# smd-practice-manufactured-2016-10-13.net
KiCad netlist of a schematic drawn in EAGLE
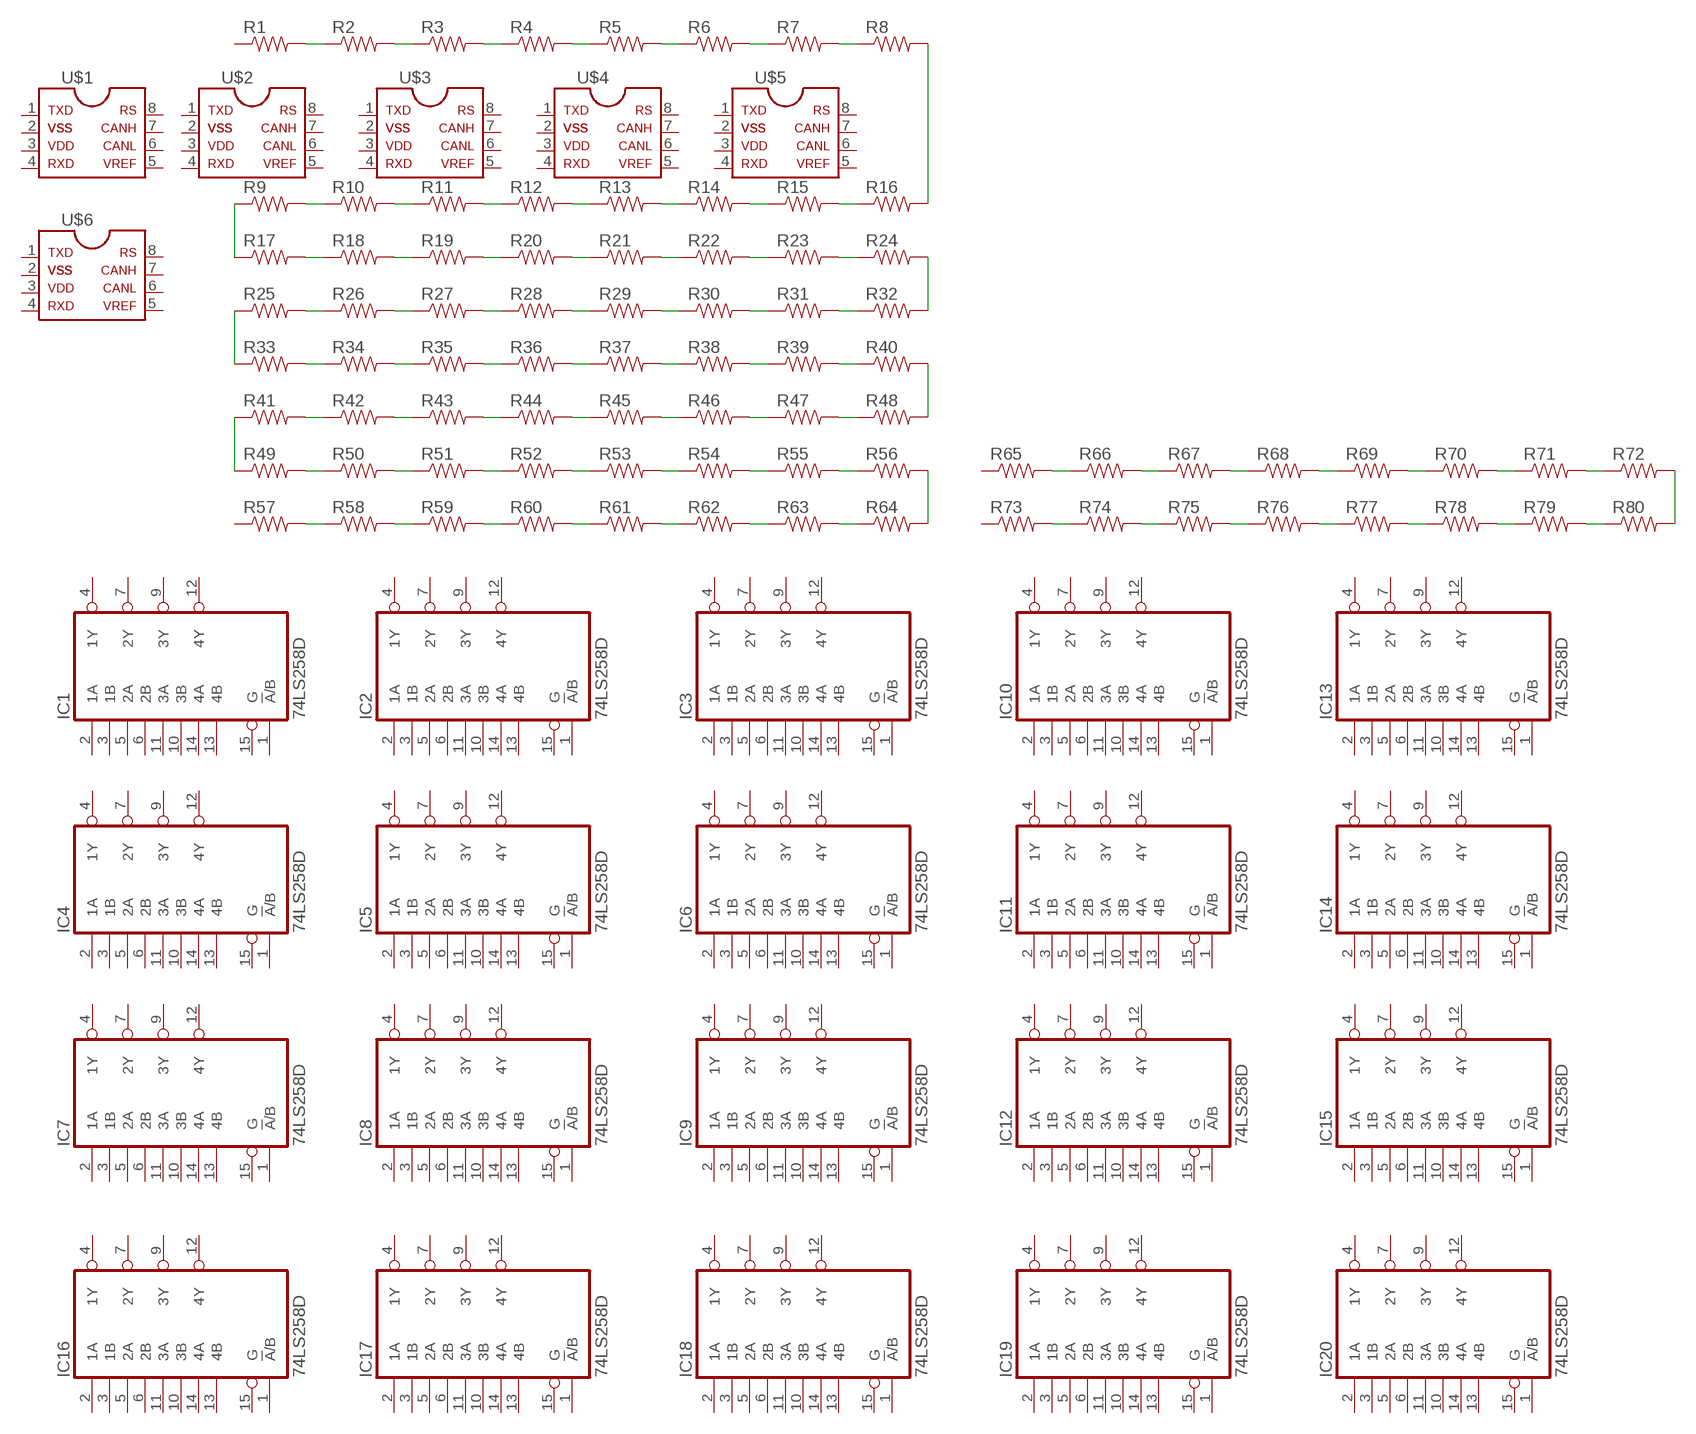
[diagram p0: schematic, sheet 1]

(export (version "E")
  (design (tool "Eeschema 10.0.6"))
  (components
    (comp (ref "IC1")
      (value "74LS258D")
      (footprint "eagle-import:SO16")
      (libsource (lib "eagle-import") (part "74258DLS"))
    )
    (comp (ref "IC2")
      (value "74LS258D")
      (footprint "eagle-import:SO16")
      (libsource (lib "eagle-import") (part "74258DLS"))
    )
    (comp (ref "IC3")
      (value "74LS258D")
      (footprint "eagle-import:SO16")
      (libsource (lib "eagle-import") (part "74258DLS"))
    )
    (comp (ref "IC4")
      (value "74LS258D")
      (footprint "eagle-import:SO16")
      (libsource (lib "eagle-import") (part "74258DLS"))
    )
    (comp (ref "IC5")
      (value "74LS258D")
      (footprint "eagle-import:SO16")
      (libsource (lib "eagle-import") (part "74258DLS"))
    )
    (comp (ref "IC6")
      (value "74LS258D")
      (footprint "eagle-import:SO16")
      (libsource (lib "eagle-import") (part "74258DLS"))
    )
    (comp (ref "IC7")
      (value "74LS258D")
      (footprint "eagle-import:SO16")
      (libsource (lib "eagle-import") (part "74258DLS"))
    )
    (comp (ref "IC8")
      (value "74LS258D")
      (footprint "eagle-import:SO16")
      (libsource (lib "eagle-import") (part "74258DLS"))
    )
    (comp (ref "IC9")
      (value "74LS258D")
      (footprint "eagle-import:SO16")
      (libsource (lib "eagle-import") (part "74258DLS"))
    )
    (comp (ref "IC10")
      (value "74LS258D")
      (footprint "eagle-import:SO16")
      (libsource (lib "eagle-import") (part "74258DLS"))
    )
    (comp (ref "IC11")
      (value "74LS258D")
      (footprint "eagle-import:SO16")
      (libsource (lib "eagle-import") (part "74258DLS"))
    )
    (comp (ref "IC12")
      (value "74LS258D")
      (footprint "eagle-import:SO16")
      (libsource (lib "eagle-import") (part "74258DLS"))
    )
    (comp (ref "IC13")
      (value "74LS258D")
      (footprint "eagle-import:SO16")
      (libsource (lib "eagle-import") (part "74258DLS"))
    )
    (comp (ref "IC14")
      (value "74LS258D")
      (footprint "eagle-import:SO16")
      (libsource (lib "eagle-import") (part "74258DLS"))
    )
    (comp (ref "IC15")
      (value "74LS258D")
      (footprint "eagle-import:SO16")
      (libsource (lib "eagle-import") (part "74258DLS"))
    )
    (comp (ref "IC16")
      (value "74LS258D")
      (footprint "eagle-import:SO16")
      (libsource (lib "eagle-import") (part "74258DLS"))
    )
    (comp (ref "IC17")
      (value "74LS258D")
      (footprint "eagle-import:SO16")
      (libsource (lib "eagle-import") (part "74258DLS"))
    )
    (comp (ref "IC18")
      (value "74LS258D")
      (footprint "eagle-import:SO16")
      (libsource (lib "eagle-import") (part "74258DLS"))
    )
    (comp (ref "IC19")
      (value "74LS258D")
      (footprint "eagle-import:SO16")
      (libsource (lib "eagle-import") (part "74258DLS"))
    )
    (comp (ref "IC20")
      (value "74LS258D")
      (footprint "eagle-import:SO16")
      (libsource (lib "eagle-import") (part "74258DLS"))
    )
    (comp (ref "R1")
      (value "RESISTOR0805-RES")
      (footprint "eagle-import:0805")
      (libsource (lib "eagle-import") (part "RESISTOR0805-RES"))
    )
    (comp (ref "R2")
      (value "RESISTOR0805-RES")
      (footprint "eagle-import:0805")
      (libsource (lib "eagle-import") (part "RESISTOR0805-RES"))
    )
    (comp (ref "R3")
      (value "RESISTOR0805-RES")
      (footprint "eagle-import:0805")
      (libsource (lib "eagle-import") (part "RESISTOR0805-RES"))
    )
    (comp (ref "R4")
      (value "RESISTOR0805-RES")
      (footprint "eagle-import:0805")
      (libsource (lib "eagle-import") (part "RESISTOR0805-RES"))
    )
    (comp (ref "R5")
      (value "RESISTOR0805-RES")
      (footprint "eagle-import:0805")
      (libsource (lib "eagle-import") (part "RESISTOR0805-RES"))
    )
    (comp (ref "R6")
      (value "RESISTOR0805-RES")
      (footprint "eagle-import:0805")
      (libsource (lib "eagle-import") (part "RESISTOR0805-RES"))
    )
    (comp (ref "R7")
      (value "RESISTOR0805-RES")
      (footprint "eagle-import:0805")
      (libsource (lib "eagle-import") (part "RESISTOR0805-RES"))
    )
    (comp (ref "R8")
      (value "RESISTOR0805-RES")
      (footprint "eagle-import:0805")
      (libsource (lib "eagle-import") (part "RESISTOR0805-RES"))
    )
    (comp (ref "R9")
      (value "RESISTOR0805-RES")
      (footprint "eagle-import:0805")
      (libsource (lib "eagle-import") (part "RESISTOR0805-RES"))
    )
    (comp (ref "R10")
      (value "RESISTOR0805-RES")
      (footprint "eagle-import:0805")
      (libsource (lib "eagle-import") (part "RESISTOR0805-RES"))
    )
    (comp (ref "R11")
      (value "RESISTOR0805-RES")
      (footprint "eagle-import:0805")
      (libsource (lib "eagle-import") (part "RESISTOR0805-RES"))
    )
    (comp (ref "R12")
      (value "RESISTOR0805-RES")
      (footprint "eagle-import:0805")
      (libsource (lib "eagle-import") (part "RESISTOR0805-RES"))
    )
    (comp (ref "R13")
      (value "RESISTOR0805-RES")
      (footprint "eagle-import:0805")
      (libsource (lib "eagle-import") (part "RESISTOR0805-RES"))
    )
    (comp (ref "R14")
      (value "RESISTOR0805-RES")
      (footprint "eagle-import:0805")
      (libsource (lib "eagle-import") (part "RESISTOR0805-RES"))
    )
    (comp (ref "R15")
      (value "RESISTOR0805-RES")
      (footprint "eagle-import:0805")
      (libsource (lib "eagle-import") (part "RESISTOR0805-RES"))
    )
    (comp (ref "R16")
      (value "RESISTOR0805-RES")
      (footprint "eagle-import:0805")
      (libsource (lib "eagle-import") (part "RESISTOR0805-RES"))
    )
    (comp (ref "R17")
      (value "RESISTOR0805-RES")
      (footprint "eagle-import:0805")
      (libsource (lib "eagle-import") (part "RESISTOR0805-RES"))
    )
    (comp (ref "R18")
      (value "RESISTOR0805-RES")
      (footprint "eagle-import:0805")
      (libsource (lib "eagle-import") (part "RESISTOR0805-RES"))
    )
    (comp (ref "R19")
      (value "RESISTOR0805-RES")
      (footprint "eagle-import:0805")
      (libsource (lib "eagle-import") (part "RESISTOR0805-RES"))
    )
    (comp (ref "R20")
      (value "RESISTOR0805-RES")
      (footprint "eagle-import:0805")
      (libsource (lib "eagle-import") (part "RESISTOR0805-RES"))
    )
    (comp (ref "R21")
      (value "RESISTOR0805-RES")
      (footprint "eagle-import:0805")
      (libsource (lib "eagle-import") (part "RESISTOR0805-RES"))
    )
    (comp (ref "R22")
      (value "RESISTOR0805-RES")
      (footprint "eagle-import:0805")
      (libsource (lib "eagle-import") (part "RESISTOR0805-RES"))
    )
    (comp (ref "R23")
      (value "RESISTOR0805-RES")
      (footprint "eagle-import:0805")
      (libsource (lib "eagle-import") (part "RESISTOR0805-RES"))
    )
    (comp (ref "R24")
      (value "RESISTOR0805-RES")
      (footprint "eagle-import:0805")
      (libsource (lib "eagle-import") (part "RESISTOR0805-RES"))
    )
    (comp (ref "R25")
      (value "RESISTOR0805-RES")
      (footprint "eagle-import:0805")
      (libsource (lib "eagle-import") (part "RESISTOR0805-RES"))
    )
    (comp (ref "R26")
      (value "RESISTOR0805-RES")
      (footprint "eagle-import:0805")
      (libsource (lib "eagle-import") (part "RESISTOR0805-RES"))
    )
    (comp (ref "R27")
      (value "RESISTOR0805-RES")
      (footprint "eagle-import:0805")
      (libsource (lib "eagle-import") (part "RESISTOR0805-RES"))
    )
    (comp (ref "R28")
      (value "RESISTOR0805-RES")
      (footprint "eagle-import:0805")
      (libsource (lib "eagle-import") (part "RESISTOR0805-RES"))
    )
    (comp (ref "R29")
      (value "RESISTOR0805-RES")
      (footprint "eagle-import:0805")
      (libsource (lib "eagle-import") (part "RESISTOR0805-RES"))
    )
    (comp (ref "R30")
      (value "RESISTOR0805-RES")
      (footprint "eagle-import:0805")
      (libsource (lib "eagle-import") (part "RESISTOR0805-RES"))
    )
    (comp (ref "R31")
      (value "RESISTOR0805-RES")
      (footprint "eagle-import:0805")
      (libsource (lib "eagle-import") (part "RESISTOR0805-RES"))
    )
    (comp (ref "R32")
      (value "RESISTOR0805-RES")
      (footprint "eagle-import:0805")
      (libsource (lib "eagle-import") (part "RESISTOR0805-RES"))
    )
    (comp (ref "R33")
      (value "RESISTOR0805-RES")
      (footprint "eagle-import:0805")
      (libsource (lib "eagle-import") (part "RESISTOR0805-RES"))
    )
    (comp (ref "R34")
      (value "RESISTOR0805-RES")
      (footprint "eagle-import:0805")
      (libsource (lib "eagle-import") (part "RESISTOR0805-RES"))
    )
    (comp (ref "R35")
      (value "RESISTOR0805-RES")
      (footprint "eagle-import:0805")
      (libsource (lib "eagle-import") (part "RESISTOR0805-RES"))
    )
    (comp (ref "R36")
      (value "RESISTOR0805-RES")
      (footprint "eagle-import:0805")
      (libsource (lib "eagle-import") (part "RESISTOR0805-RES"))
    )
    (comp (ref "R37")
      (value "RESISTOR0805-RES")
      (footprint "eagle-import:0805")
      (libsource (lib "eagle-import") (part "RESISTOR0805-RES"))
    )
    (comp (ref "R38")
      (value "RESISTOR0805-RES")
      (footprint "eagle-import:0805")
      (libsource (lib "eagle-import") (part "RESISTOR0805-RES"))
    )
    (comp (ref "R39")
      (value "RESISTOR0805-RES")
      (footprint "eagle-import:0805")
      (libsource (lib "eagle-import") (part "RESISTOR0805-RES"))
    )
    (comp (ref "R40")
      (value "RESISTOR0805-RES")
      (footprint "eagle-import:0805")
      (libsource (lib "eagle-import") (part "RESISTOR0805-RES"))
    )
    (comp (ref "R41")
      (value "RESISTOR0805-RES")
      (footprint "eagle-import:0805")
      (libsource (lib "eagle-import") (part "RESISTOR0805-RES"))
    )
    (comp (ref "R42")
      (value "RESISTOR0805-RES")
      (footprint "eagle-import:0805")
      (libsource (lib "eagle-import") (part "RESISTOR0805-RES"))
    )
    (comp (ref "R43")
      (value "RESISTOR0805-RES")
      (footprint "eagle-import:0805")
      (libsource (lib "eagle-import") (part "RESISTOR0805-RES"))
    )
    (comp (ref "R44")
      (value "RESISTOR0805-RES")
      (footprint "eagle-import:0805")
      (libsource (lib "eagle-import") (part "RESISTOR0805-RES"))
    )
    (comp (ref "R45")
      (value "RESISTOR0805-RES")
      (footprint "eagle-import:0805")
      (libsource (lib "eagle-import") (part "RESISTOR0805-RES"))
    )
    (comp (ref "R46")
      (value "RESISTOR0805-RES")
      (footprint "eagle-import:0805")
      (libsource (lib "eagle-import") (part "RESISTOR0805-RES"))
    )
    (comp (ref "R47")
      (value "RESISTOR0805-RES")
      (footprint "eagle-import:0805")
      (libsource (lib "eagle-import") (part "RESISTOR0805-RES"))
    )
    (comp (ref "R48")
      (value "RESISTOR0805-RES")
      (footprint "eagle-import:0805")
      (libsource (lib "eagle-import") (part "RESISTOR0805-RES"))
    )
    (comp (ref "R49")
      (value "RESISTOR0805-RES")
      (footprint "eagle-import:0805")
      (libsource (lib "eagle-import") (part "RESISTOR0805-RES"))
    )
    (comp (ref "R50")
      (value "RESISTOR0805-RES")
      (footprint "eagle-import:0805")
      (libsource (lib "eagle-import") (part "RESISTOR0805-RES"))
    )
    (comp (ref "R51")
      (value "RESISTOR0805-RES")
      (footprint "eagle-import:0805")
      (libsource (lib "eagle-import") (part "RESISTOR0805-RES"))
    )
    (comp (ref "R52")
      (value "RESISTOR0805-RES")
      (footprint "eagle-import:0805")
      (libsource (lib "eagle-import") (part "RESISTOR0805-RES"))
    )
    (comp (ref "R53")
      (value "RESISTOR0805-RES")
      (footprint "eagle-import:0805")
      (libsource (lib "eagle-import") (part "RESISTOR0805-RES"))
    )
    (comp (ref "R54")
      (value "RESISTOR0805-RES")
      (footprint "eagle-import:0805")
      (libsource (lib "eagle-import") (part "RESISTOR0805-RES"))
    )
    (comp (ref "R55")
      (value "RESISTOR0805-RES")
      (footprint "eagle-import:0805")
      (libsource (lib "eagle-import") (part "RESISTOR0805-RES"))
    )
    (comp (ref "R56")
      (value "RESISTOR0805-RES")
      (footprint "eagle-import:0805")
      (libsource (lib "eagle-import") (part "RESISTOR0805-RES"))
    )
    (comp (ref "R57")
      (value "RESISTOR0805-RES")
      (footprint "eagle-import:0805")
      (libsource (lib "eagle-import") (part "RESISTOR0805-RES"))
    )
    (comp (ref "R58")
      (value "RESISTOR0805-RES")
      (footprint "eagle-import:0805")
      (libsource (lib "eagle-import") (part "RESISTOR0805-RES"))
    )
    (comp (ref "R59")
      (value "RESISTOR0805-RES")
      (footprint "eagle-import:0805")
      (libsource (lib "eagle-import") (part "RESISTOR0805-RES"))
    )
    (comp (ref "R60")
      (value "RESISTOR0805-RES")
      (footprint "eagle-import:0805")
      (libsource (lib "eagle-import") (part "RESISTOR0805-RES"))
    )
    (comp (ref "R61")
      (value "RESISTOR0805-RES")
      (footprint "eagle-import:0805")
      (libsource (lib "eagle-import") (part "RESISTOR0805-RES"))
    )
    (comp (ref "R62")
      (value "RESISTOR0805-RES")
      (footprint "eagle-import:0805")
      (libsource (lib "eagle-import") (part "RESISTOR0805-RES"))
    )
    (comp (ref "R63")
      (value "RESISTOR0805-RES")
      (footprint "eagle-import:0805")
      (libsource (lib "eagle-import") (part "RESISTOR0805-RES"))
    )
    (comp (ref "R64")
      (value "RESISTOR0805-RES")
      (footprint "eagle-import:0805")
      (libsource (lib "eagle-import") (part "RESISTOR0805-RES"))
    )
    (comp (ref "R65")
      (value "RESISTOR0805-RES")
      (footprint "eagle-import:0805")
      (libsource (lib "eagle-import") (part "RESISTOR0805-RES"))
    )
    (comp (ref "R66")
      (value "RESISTOR0805-RES")
      (footprint "eagle-import:0805")
      (libsource (lib "eagle-import") (part "RESISTOR0805-RES"))
    )
    (comp (ref "R67")
      (value "RESISTOR0805-RES")
      (footprint "eagle-import:0805")
      (libsource (lib "eagle-import") (part "RESISTOR0805-RES"))
    )
    (comp (ref "R68")
      (value "RESISTOR0805-RES")
      (footprint "eagle-import:0805")
      (libsource (lib "eagle-import") (part "RESISTOR0805-RES"))
    )
    (comp (ref "R69")
      (value "RESISTOR0805-RES")
      (footprint "eagle-import:0805")
      (libsource (lib "eagle-import") (part "RESISTOR0805-RES"))
    )
    (comp (ref "R70")
      (value "RESISTOR0805-RES")
      (footprint "eagle-import:0805")
      (libsource (lib "eagle-import") (part "RESISTOR0805-RES"))
    )
    (comp (ref "R71")
      (value "RESISTOR0805-RES")
      (footprint "eagle-import:0805")
      (libsource (lib "eagle-import") (part "RESISTOR0805-RES"))
    )
    (comp (ref "R72")
      (value "RESISTOR0805-RES")
      (footprint "eagle-import:0805")
      (libsource (lib "eagle-import") (part "RESISTOR0805-RES"))
    )
    (comp (ref "R73")
      (value "RESISTOR0805-RES")
      (footprint "eagle-import:0805")
      (libsource (lib "eagle-import") (part "RESISTOR0805-RES"))
    )
    (comp (ref "R74")
      (value "RESISTOR0805-RES")
      (footprint "eagle-import:0805")
      (libsource (lib "eagle-import") (part "RESISTOR0805-RES"))
    )
    (comp (ref "R75")
      (value "RESISTOR0805-RES")
      (footprint "eagle-import:0805")
      (libsource (lib "eagle-import") (part "RESISTOR0805-RES"))
    )
    (comp (ref "R76")
      (value "RESISTOR0805-RES")
      (footprint "eagle-import:0805")
      (libsource (lib "eagle-import") (part "RESISTOR0805-RES"))
    )
    (comp (ref "R77")
      (value "RESISTOR0805-RES")
      (footprint "eagle-import:0805")
      (libsource (lib "eagle-import") (part "RESISTOR0805-RES"))
    )
    (comp (ref "R78")
      (value "RESISTOR0805-RES")
      (footprint "eagle-import:0805")
      (libsource (lib "eagle-import") (part "RESISTOR0805-RES"))
    )
    (comp (ref "R79")
      (value "RESISTOR0805-RES")
      (footprint "eagle-import:0805")
      (libsource (lib "eagle-import") (part "RESISTOR0805-RES"))
    )
    (comp (ref "R80")
      (value "RESISTOR0805-RES")
      (footprint "eagle-import:0805")
      (libsource (lib "eagle-import") (part "RESISTOR0805-RES"))
    )
    (comp (ref "U$1")
      (value "MCP2551")
      (footprint "eagle-import:SOIC-08")
      (libsource (lib "eagle-import") (part "MCP2551"))
    )
    (comp (ref "U$2")
      (value "MCP2551")
      (footprint "eagle-import:SOIC-08")
      (libsource (lib "eagle-import") (part "MCP2551"))
    )
    (comp (ref "U$3")
      (value "MCP2551")
      (footprint "eagle-import:SOIC-08")
      (libsource (lib "eagle-import") (part "MCP2551"))
    )
    (comp (ref "U$4")
      (value "MCP2551")
      (footprint "eagle-import:SOIC-08")
      (libsource (lib "eagle-import") (part "MCP2551"))
    )
    (comp (ref "U$5")
      (value "MCP2551")
      (footprint "eagle-import:SOIC-08")
      (libsource (lib "eagle-import") (part "MCP2551"))
    )
    (comp (ref "U$6")
      (value "MCP2551")
      (footprint "eagle-import:SOIC-08")
      (libsource (lib "eagle-import") (part "MCP2551"))
    )
  )
  (nets
    (net (code "1") (name "Net-(R1-Pad2)") (class "Default")
      (node (ref "R1") (pin "2") (pinfunction "2_2") (pintype "passive"))
      (node (ref "R2") (pin "1") (pinfunction "1_1") (pintype "passive"))
    )
    (net (code "2") (name "Net-(R2-Pad2)") (class "Default")
      (node (ref "R2") (pin "2") (pinfunction "2_2") (pintype "passive"))
      (node (ref "R3") (pin "1") (pinfunction "1_1") (pintype "passive"))
    )
    (net (code "3") (name "Net-(R3-Pad2)") (class "Default")
      (node (ref "R3") (pin "2") (pinfunction "2_2") (pintype "passive"))
      (node (ref "R4") (pin "1") (pinfunction "1_1") (pintype "passive"))
    )
    (net (code "4") (name "Net-(R4-Pad2)") (class "Default")
      (node (ref "R4") (pin "2") (pinfunction "2_2") (pintype "passive"))
      (node (ref "R5") (pin "1") (pinfunction "1_1") (pintype "passive"))
    )
    (net (code "5") (name "Net-(R5-Pad2)") (class "Default")
      (node (ref "R5") (pin "2") (pinfunction "2_2") (pintype "passive"))
      (node (ref "R6") (pin "1") (pinfunction "1_1") (pintype "passive"))
    )
    (net (code "6") (name "Net-(R6-Pad2)") (class "Default")
      (node (ref "R6") (pin "2") (pinfunction "2_2") (pintype "passive"))
      (node (ref "R7") (pin "1") (pinfunction "1_1") (pintype "passive"))
    )
    (net (code "7") (name "Net-(R7-Pad2)") (class "Default")
      (node (ref "R7") (pin "2") (pinfunction "2_2") (pintype "passive"))
      (node (ref "R8") (pin "1") (pinfunction "1_1") (pintype "passive"))
    )
    (net (code "8") (name "Net-(R10-Pad1)") (class "Default")
      (node (ref "R10") (pin "1") (pinfunction "1_1") (pintype "passive"))
      (node (ref "R9") (pin "2") (pinfunction "2_2") (pintype "passive"))
    )
    (net (code "9") (name "Net-(R10-Pad2)") (class "Default")
      (node (ref "R10") (pin "2") (pinfunction "2_2") (pintype "passive"))
      (node (ref "R11") (pin "1") (pinfunction "1_1") (pintype "passive"))
    )
    (net (code "10") (name "Net-(R11-Pad2)") (class "Default")
      (node (ref "R11") (pin "2") (pinfunction "2_2") (pintype "passive"))
      (node (ref "R12") (pin "1") (pinfunction "1_1") (pintype "passive"))
    )
    (net (code "11") (name "Net-(R12-Pad2)") (class "Default")
      (node (ref "R12") (pin "2") (pinfunction "2_2") (pintype "passive"))
      (node (ref "R13") (pin "1") (pinfunction "1_1") (pintype "passive"))
    )
    (net (code "12") (name "Net-(R13-Pad2)") (class "Default")
      (node (ref "R13") (pin "2") (pinfunction "2_2") (pintype "passive"))
      (node (ref "R14") (pin "1") (pinfunction "1_1") (pintype "passive"))
    )
    (net (code "13") (name "Net-(R14-Pad2)") (class "Default")
      (node (ref "R14") (pin "2") (pinfunction "2_2") (pintype "passive"))
      (node (ref "R15") (pin "1") (pinfunction "1_1") (pintype "passive"))
    )
    (net (code "14") (name "Net-(R15-Pad2)") (class "Default")
      (node (ref "R15") (pin "2") (pinfunction "2_2") (pintype "passive"))
      (node (ref "R16") (pin "1") (pinfunction "1_1") (pintype "passive"))
    )
    (net (code "15") (name "Net-(R16-Pad2)") (class "Default")
      (node (ref "R16") (pin "2") (pinfunction "2_2") (pintype "passive"))
      (node (ref "R8") (pin "2") (pinfunction "2_2") (pintype "passive"))
    )
    (net (code "16") (name "Net-(R17-Pad1)") (class "Default")
      (node (ref "R17") (pin "1") (pinfunction "1_1") (pintype "passive"))
      (node (ref "R9") (pin "1") (pinfunction "1_1") (pintype "passive"))
    )
    (net (code "17") (name "Net-(R17-Pad2)") (class "Default")
      (node (ref "R17") (pin "2") (pinfunction "2_2") (pintype "passive"))
      (node (ref "R18") (pin "1") (pinfunction "1_1") (pintype "passive"))
    )
    (net (code "18") (name "Net-(R18-Pad2)") (class "Default")
      (node (ref "R18") (pin "2") (pinfunction "2_2") (pintype "passive"))
      (node (ref "R19") (pin "1") (pinfunction "1_1") (pintype "passive"))
    )
    (net (code "19") (name "Net-(R19-Pad2)") (class "Default")
      (node (ref "R19") (pin "2") (pinfunction "2_2") (pintype "passive"))
      (node (ref "R20") (pin "1") (pinfunction "1_1") (pintype "passive"))
    )
    (net (code "20") (name "Net-(R20-Pad2)") (class "Default")
      (node (ref "R20") (pin "2") (pinfunction "2_2") (pintype "passive"))
      (node (ref "R21") (pin "1") (pinfunction "1_1") (pintype "passive"))
    )
    (net (code "21") (name "Net-(R21-Pad2)") (class "Default")
      (node (ref "R21") (pin "2") (pinfunction "2_2") (pintype "passive"))
      (node (ref "R22") (pin "1") (pinfunction "1_1") (pintype "passive"))
    )
    (net (code "22") (name "Net-(R22-Pad2)") (class "Default")
      (node (ref "R22") (pin "2") (pinfunction "2_2") (pintype "passive"))
      (node (ref "R23") (pin "1") (pinfunction "1_1") (pintype "passive"))
    )
    (net (code "23") (name "Net-(R23-Pad2)") (class "Default")
      (node (ref "R23") (pin "2") (pinfunction "2_2") (pintype "passive"))
      (node (ref "R24") (pin "1") (pinfunction "1_1") (pintype "passive"))
    )
    (net (code "24") (name "Net-(R24-Pad2)") (class "Default")
      (node (ref "R24") (pin "2") (pinfunction "2_2") (pintype "passive"))
      (node (ref "R32") (pin "2") (pinfunction "2_2") (pintype "passive"))
    )
    (net (code "25") (name "Net-(R25-Pad1)") (class "Default")
      (node (ref "R25") (pin "1") (pinfunction "1_1") (pintype "passive"))
      (node (ref "R33") (pin "1") (pinfunction "1_1") (pintype "passive"))
    )
    (net (code "26") (name "Net-(R25-Pad2)") (class "Default")
      (node (ref "R25") (pin "2") (pinfunction "2_2") (pintype "passive"))
      (node (ref "R26") (pin "1") (pinfunction "1_1") (pintype "passive"))
    )
    (net (code "27") (name "Net-(R26-Pad2)") (class "Default")
      (node (ref "R26") (pin "2") (pinfunction "2_2") (pintype "passive"))
      (node (ref "R27") (pin "1") (pinfunction "1_1") (pintype "passive"))
    )
    (net (code "28") (name "Net-(R27-Pad2)") (class "Default")
      (node (ref "R27") (pin "2") (pinfunction "2_2") (pintype "passive"))
      (node (ref "R28") (pin "1") (pinfunction "1_1") (pintype "passive"))
    )
    (net (code "29") (name "Net-(R28-Pad2)") (class "Default")
      (node (ref "R28") (pin "2") (pinfunction "2_2") (pintype "passive"))
      (node (ref "R29") (pin "1") (pinfunction "1_1") (pintype "passive"))
    )
    (net (code "30") (name "Net-(R29-Pad2)") (class "Default")
      (node (ref "R29") (pin "2") (pinfunction "2_2") (pintype "passive"))
      (node (ref "R30") (pin "1") (pinfunction "1_1") (pintype "passive"))
    )
    (net (code "31") (name "Net-(R30-Pad2)") (class "Default")
      (node (ref "R30") (pin "2") (pinfunction "2_2") (pintype "passive"))
      (node (ref "R31") (pin "1") (pinfunction "1_1") (pintype "passive"))
    )
    (net (code "32") (name "Net-(R31-Pad2)") (class "Default")
      (node (ref "R31") (pin "2") (pinfunction "2_2") (pintype "passive"))
      (node (ref "R32") (pin "1") (pinfunction "1_1") (pintype "passive"))
    )
    (net (code "33") (name "Net-(R33-Pad2)") (class "Default")
      (node (ref "R33") (pin "2") (pinfunction "2_2") (pintype "passive"))
      (node (ref "R34") (pin "1") (pinfunction "1_1") (pintype "passive"))
    )
    (net (code "34") (name "Net-(R34-Pad2)") (class "Default")
      (node (ref "R34") (pin "2") (pinfunction "2_2") (pintype "passive"))
      (node (ref "R35") (pin "1") (pinfunction "1_1") (pintype "passive"))
    )
    (net (code "35") (name "Net-(R35-Pad2)") (class "Default")
      (node (ref "R35") (pin "2") (pinfunction "2_2") (pintype "passive"))
      (node (ref "R36") (pin "1") (pinfunction "1_1") (pintype "passive"))
    )
    (net (code "36") (name "Net-(R36-Pad2)") (class "Default")
      (node (ref "R36") (pin "2") (pinfunction "2_2") (pintype "passive"))
      (node (ref "R37") (pin "1") (pinfunction "1_1") (pintype "passive"))
    )
    (net (code "37") (name "Net-(R37-Pad2)") (class "Default")
      (node (ref "R37") (pin "2") (pinfunction "2_2") (pintype "passive"))
      (node (ref "R38") (pin "1") (pinfunction "1_1") (pintype "passive"))
    )
    (net (code "38") (name "Net-(R38-Pad2)") (class "Default")
      (node (ref "R38") (pin "2") (pinfunction "2_2") (pintype "passive"))
      (node (ref "R39") (pin "1") (pinfunction "1_1") (pintype "passive"))
    )
    (net (code "39") (name "Net-(R39-Pad2)") (class "Default")
      (node (ref "R39") (pin "2") (pinfunction "2_2") (pintype "passive"))
      (node (ref "R40") (pin "1") (pinfunction "1_1") (pintype "passive"))
    )
    (net (code "40") (name "Net-(R40-Pad2)") (class "Default")
      (node (ref "R40") (pin "2") (pinfunction "2_2") (pintype "passive"))
      (node (ref "R48") (pin "2") (pinfunction "2_2") (pintype "passive"))
    )
    (net (code "41") (name "Net-(R41-Pad1)") (class "Default")
      (node (ref "R41") (pin "1") (pinfunction "1_1") (pintype "passive"))
      (node (ref "R49") (pin "1") (pinfunction "1_1") (pintype "passive"))
    )
    (net (code "42") (name "Net-(R41-Pad2)") (class "Default")
      (node (ref "R41") (pin "2") (pinfunction "2_2") (pintype "passive"))
      (node (ref "R42") (pin "1") (pinfunction "1_1") (pintype "passive"))
    )
    (net (code "43") (name "Net-(R42-Pad2)") (class "Default")
      (node (ref "R42") (pin "2") (pinfunction "2_2") (pintype "passive"))
      (node (ref "R43") (pin "1") (pinfunction "1_1") (pintype "passive"))
    )
    (net (code "44") (name "Net-(R43-Pad2)") (class "Default")
      (node (ref "R43") (pin "2") (pinfunction "2_2") (pintype "passive"))
      (node (ref "R44") (pin "1") (pinfunction "1_1") (pintype "passive"))
    )
    (net (code "45") (name "Net-(R44-Pad2)") (class "Default")
      (node (ref "R44") (pin "2") (pinfunction "2_2") (pintype "passive"))
      (node (ref "R45") (pin "1") (pinfunction "1_1") (pintype "passive"))
    )
    (net (code "46") (name "Net-(R45-Pad2)") (class "Default")
      (node (ref "R45") (pin "2") (pinfunction "2_2") (pintype "passive"))
      (node (ref "R46") (pin "1") (pinfunction "1_1") (pintype "passive"))
    )
    (net (code "47") (name "Net-(R46-Pad2)") (class "Default")
      (node (ref "R46") (pin "2") (pinfunction "2_2") (pintype "passive"))
      (node (ref "R47") (pin "1") (pinfunction "1_1") (pintype "passive"))
    )
    (net (code "48") (name "Net-(R47-Pad2)") (class "Default")
      (node (ref "R47") (pin "2") (pinfunction "2_2") (pintype "passive"))
      (node (ref "R48") (pin "1") (pinfunction "1_1") (pintype "passive"))
    )
    (net (code "49") (name "Net-(R49-Pad2)") (class "Default")
      (node (ref "R49") (pin "2") (pinfunction "2_2") (pintype "passive"))
      (node (ref "R50") (pin "1") (pinfunction "1_1") (pintype "passive"))
    )
    (net (code "50") (name "Net-(R50-Pad2)") (class "Default")
      (node (ref "R50") (pin "2") (pinfunction "2_2") (pintype "passive"))
      (node (ref "R51") (pin "1") (pinfunction "1_1") (pintype "passive"))
    )
    (net (code "51") (name "Net-(R51-Pad2)") (class "Default")
      (node (ref "R51") (pin "2") (pinfunction "2_2") (pintype "passive"))
      (node (ref "R52") (pin "1") (pinfunction "1_1") (pintype "passive"))
    )
    (net (code "52") (name "Net-(R52-Pad2)") (class "Default")
      (node (ref "R52") (pin "2") (pinfunction "2_2") (pintype "passive"))
      (node (ref "R53") (pin "1") (pinfunction "1_1") (pintype "passive"))
    )
    (net (code "53") (name "Net-(R53-Pad2)") (class "Default")
      (node (ref "R53") (pin "2") (pinfunction "2_2") (pintype "passive"))
      (node (ref "R54") (pin "1") (pinfunction "1_1") (pintype "passive"))
    )
    (net (code "54") (name "Net-(R54-Pad2)") (class "Default")
      (node (ref "R54") (pin "2") (pinfunction "2_2") (pintype "passive"))
      (node (ref "R55") (pin "1") (pinfunction "1_1") (pintype "passive"))
    )
    (net (code "55") (name "Net-(R55-Pad2)") (class "Default")
      (node (ref "R55") (pin "2") (pinfunction "2_2") (pintype "passive"))
      (node (ref "R56") (pin "1") (pinfunction "1_1") (pintype "passive"))
    )
    (net (code "56") (name "Net-(R56-Pad2)") (class "Default")
      (node (ref "R56") (pin "2") (pinfunction "2_2") (pintype "passive"))
      (node (ref "R64") (pin "2") (pinfunction "2_2") (pintype "passive"))
    )
    (net (code "57") (name "Net-(R57-Pad2)") (class "Default")
      (node (ref "R57") (pin "2") (pinfunction "2_2") (pintype "passive"))
      (node (ref "R58") (pin "1") (pinfunction "1_1") (pintype "passive"))
    )
    (net (code "58") (name "Net-(R58-Pad2)") (class "Default")
      (node (ref "R58") (pin "2") (pinfunction "2_2") (pintype "passive"))
      (node (ref "R59") (pin "1") (pinfunction "1_1") (pintype "passive"))
    )
    (net (code "59") (name "Net-(R59-Pad2)") (class "Default")
      (node (ref "R59") (pin "2") (pinfunction "2_2") (pintype "passive"))
      (node (ref "R60") (pin "1") (pinfunction "1_1") (pintype "passive"))
    )
    (net (code "60") (name "Net-(R60-Pad2)") (class "Default")
      (node (ref "R60") (pin "2") (pinfunction "2_2") (pintype "passive"))
      (node (ref "R61") (pin "1") (pinfunction "1_1") (pintype "passive"))
    )
    (net (code "61") (name "Net-(R61-Pad2)") (class "Default")
      (node (ref "R61") (pin "2") (pinfunction "2_2") (pintype "passive"))
      (node (ref "R62") (pin "1") (pinfunction "1_1") (pintype "passive"))
    )
    (net (code "62") (name "Net-(R62-Pad2)") (class "Default")
      (node (ref "R62") (pin "2") (pinfunction "2_2") (pintype "passive"))
      (node (ref "R63") (pin "1") (pinfunction "1_1") (pintype "passive"))
    )
    (net (code "63") (name "Net-(R63-Pad2)") (class "Default")
      (node (ref "R63") (pin "2") (pinfunction "2_2") (pintype "passive"))
      (node (ref "R64") (pin "1") (pinfunction "1_1") (pintype "passive"))
    )
    (net (code "64") (name "Net-(R65-Pad2)") (class "Default")
      (node (ref "R65") (pin "2") (pinfunction "2_2") (pintype "passive"))
      (node (ref "R66") (pin "1") (pinfunction "1_1") (pintype "passive"))
    )
    (net (code "65") (name "Net-(R66-Pad2)") (class "Default")
      (node (ref "R66") (pin "2") (pinfunction "2_2") (pintype "passive"))
      (node (ref "R67") (pin "1") (pinfunction "1_1") (pintype "passive"))
    )
    (net (code "66") (name "Net-(R67-Pad2)") (class "Default")
      (node (ref "R67") (pin "2") (pinfunction "2_2") (pintype "passive"))
      (node (ref "R68") (pin "1") (pinfunction "1_1") (pintype "passive"))
    )
    (net (code "67") (name "Net-(R68-Pad2)") (class "Default")
      (node (ref "R68") (pin "2") (pinfunction "2_2") (pintype "passive"))
      (node (ref "R69") (pin "1") (pinfunction "1_1") (pintype "passive"))
    )
    (net (code "68") (name "Net-(R69-Pad2)") (class "Default")
      (node (ref "R69") (pin "2") (pinfunction "2_2") (pintype "passive"))
      (node (ref "R70") (pin "1") (pinfunction "1_1") (pintype "passive"))
    )
    (net (code "69") (name "Net-(R70-Pad2)") (class "Default")
      (node (ref "R70") (pin "2") (pinfunction "2_2") (pintype "passive"))
      (node (ref "R71") (pin "1") (pinfunction "1_1") (pintype "passive"))
    )
    (net (code "70") (name "Net-(R71-Pad2)") (class "Default")
      (node (ref "R71") (pin "2") (pinfunction "2_2") (pintype "passive"))
      (node (ref "R72") (pin "1") (pinfunction "1_1") (pintype "passive"))
    )
    (net (code "71") (name "Net-(R72-Pad2)") (class "Default")
      (node (ref "R72") (pin "2") (pinfunction "2_2") (pintype "passive"))
      (node (ref "R80") (pin "2") (pinfunction "2_2") (pintype "passive"))
    )
    (net (code "72") (name "Net-(R73-Pad2)") (class "Default")
      (node (ref "R73") (pin "2") (pinfunction "2_2") (pintype "passive"))
      (node (ref "R74") (pin "1") (pinfunction "1_1") (pintype "passive"))
    )
    (net (code "73") (name "Net-(R74-Pad2)") (class "Default")
      (node (ref "R74") (pin "2") (pinfunction "2_2") (pintype "passive"))
      (node (ref "R75") (pin "1") (pinfunction "1_1") (pintype "passive"))
    )
    (net (code "74") (name "Net-(R75-Pad2)") (class "Default")
      (node (ref "R75") (pin "2") (pinfunction "2_2") (pintype "passive"))
      (node (ref "R76") (pin "1") (pinfunction "1_1") (pintype "passive"))
    )
    (net (code "75") (name "Net-(R76-Pad2)") (class "Default")
      (node (ref "R76") (pin "2") (pinfunction "2_2") (pintype "passive"))
      (node (ref "R77") (pin "1") (pinfunction "1_1") (pintype "passive"))
    )
    (net (code "76") (name "Net-(R77-Pad2)") (class "Default")
      (node (ref "R77") (pin "2") (pinfunction "2_2") (pintype "passive"))
      (node (ref "R78") (pin "1") (pinfunction "1_1") (pintype "passive"))
    )
    (net (code "77") (name "Net-(R78-Pad2)") (class "Default")
      (node (ref "R78") (pin "2") (pinfunction "2_2") (pintype "passive"))
      (node (ref "R79") (pin "1") (pinfunction "1_1") (pintype "passive"))
    )
    (net (code "78") (name "Net-(R79-Pad2)") (class "Default")
      (node (ref "R79") (pin "2") (pinfunction "2_2") (pintype "passive"))
      (node (ref "R80") (pin "1") (pinfunction "1_1") (pintype "passive"))
    )
    (net (code "79") (name "unconnected-(IC1A-1A-Pad2)") (class "Default")
      (node (ref "IC1") (pin "2") (pinfunction "1A_2") (pintype "input"))
    )
    (net (code "80") (name "unconnected-(IC1A-1B-Pad3)") (class "Default")
      (node (ref "IC1") (pin "3") (pinfunction "1B_3") (pintype "input"))
    )
    (net (code "81") (name "unconnected-(IC1A-1Y-Pad4)") (class "Default")
      (node (ref "IC1") (pin "4") (pinfunction "1Y_4") (pintype "tri_state"))
    )
    (net (code "82") (name "unconnected-(IC1A-2A-Pad5)") (class "Default")
      (node (ref "IC1") (pin "5") (pinfunction "2A_5") (pintype "input"))
    )
    (net (code "83") (name "unconnected-(IC1A-2B-Pad6)") (class "Default")
      (node (ref "IC1") (pin "6") (pinfunction "2B_6") (pintype "input"))
    )
    (net (code "84") (name "unconnected-(IC1A-2Y-Pad7)") (class "Default")
      (node (ref "IC1") (pin "7") (pinfunction "2Y_7") (pintype "tri_state"))
    )
    (net (code "85") (name "unconnected-(IC1A-3A-Pad11)") (class "Default")
      (node (ref "IC1") (pin "11") (pinfunction "3A_11") (pintype "input"))
    )
    (net (code "86") (name "unconnected-(IC1A-3B-Pad10)") (class "Default")
      (node (ref "IC1") (pin "10") (pinfunction "3B_10") (pintype "input"))
    )
    (net (code "87") (name "unconnected-(IC1A-3Y-Pad9)") (class "Default")
      (node (ref "IC1") (pin "9") (pinfunction "3Y_9") (pintype "tri_state"))
    )
    (net (code "88") (name "unconnected-(IC1A-4A-Pad14)") (class "Default")
      (node (ref "IC1") (pin "14") (pinfunction "4A_14") (pintype "input"))
    )
    (net (code "89") (name "unconnected-(IC1A-4B-Pad13)") (class "Default")
      (node (ref "IC1") (pin "13") (pinfunction "4B_13") (pintype "input"))
    )
    (net (code "90") (name "unconnected-(IC1A-4Y-Pad12)") (class "Default")
      (node (ref "IC1") (pin "12") (pinfunction "4Y_12") (pintype "tri_state"))
    )
    (net (code "91") (name "unconnected-(IC1A-G-Pad15)") (class "Default")
      (node (ref "IC1") (pin "15") (pinfunction "G_15") (pintype "input"))
    )
    (net (code "92") (name "unconnected-(IC1A-~{A}{slash}B-Pad1)") (class "Default")
      (node (ref "IC1") (pin "1") (pinfunction "~{A}/B_1") (pintype "input"))
    )
    (net (code "93") (name "unconnected-(IC2A-1A-Pad2)") (class "Default")
      (node (ref "IC2") (pin "2") (pinfunction "1A_2") (pintype "input"))
    )
    (net (code "94") (name "unconnected-(IC2A-1B-Pad3)") (class "Default")
      (node (ref "IC2") (pin "3") (pinfunction "1B_3") (pintype "input"))
    )
    (net (code "95") (name "unconnected-(IC2A-1Y-Pad4)") (class "Default")
      (node (ref "IC2") (pin "4") (pinfunction "1Y_4") (pintype "tri_state"))
    )
    (net (code "96") (name "unconnected-(IC2A-2A-Pad5)") (class "Default")
      (node (ref "IC2") (pin "5") (pinfunction "2A_5") (pintype "input"))
    )
    (net (code "97") (name "unconnected-(IC2A-2B-Pad6)") (class "Default")
      (node (ref "IC2") (pin "6") (pinfunction "2B_6") (pintype "input"))
    )
    (net (code "98") (name "unconnected-(IC2A-2Y-Pad7)") (class "Default")
      (node (ref "IC2") (pin "7") (pinfunction "2Y_7") (pintype "tri_state"))
    )
    (net (code "99") (name "unconnected-(IC2A-3A-Pad11)") (class "Default")
      (node (ref "IC2") (pin "11") (pinfunction "3A_11") (pintype "input"))
    )
    (net (code "100") (name "unconnected-(IC2A-3B-Pad10)") (class "Default")
      (node (ref "IC2") (pin "10") (pinfunction "3B_10") (pintype "input"))
    )
    (net (code "101") (name "unconnected-(IC2A-3Y-Pad9)") (class "Default")
      (node (ref "IC2") (pin "9") (pinfunction "3Y_9") (pintype "tri_state"))
    )
    (net (code "102") (name "unconnected-(IC2A-4A-Pad14)") (class "Default")
      (node (ref "IC2") (pin "14") (pinfunction "4A_14") (pintype "input"))
    )
    (net (code "103") (name "unconnected-(IC2A-4B-Pad13)") (class "Default")
      (node (ref "IC2") (pin "13") (pinfunction "4B_13") (pintype "input"))
    )
    (net (code "104") (name "unconnected-(IC2A-4Y-Pad12)") (class "Default")
      (node (ref "IC2") (pin "12") (pinfunction "4Y_12") (pintype "tri_state"))
    )
    (net (code "105") (name "unconnected-(IC2A-G-Pad15)") (class "Default")
      (node (ref "IC2") (pin "15") (pinfunction "G_15") (pintype "input"))
    )
    (net (code "106") (name "unconnected-(IC2A-~{A}{slash}B-Pad1)") (class "Default")
      (node (ref "IC2") (pin "1") (pinfunction "~{A}/B_1") (pintype "input"))
    )
    (net (code "107") (name "unconnected-(IC3A-1A-Pad2)") (class "Default")
      (node (ref "IC3") (pin "2") (pinfunction "1A_2") (pintype "input"))
    )
    (net (code "108") (name "unconnected-(IC3A-1B-Pad3)") (class "Default")
      (node (ref "IC3") (pin "3") (pinfunction "1B_3") (pintype "input"))
    )
    (net (code "109") (name "unconnected-(IC3A-1Y-Pad4)") (class "Default")
      (node (ref "IC3") (pin "4") (pinfunction "1Y_4") (pintype "tri_state"))
    )
    (net (code "110") (name "unconnected-(IC3A-2A-Pad5)") (class "Default")
      (node (ref "IC3") (pin "5") (pinfunction "2A_5") (pintype "input"))
    )
    (net (code "111") (name "unconnected-(IC3A-2B-Pad6)") (class "Default")
      (node (ref "IC3") (pin "6") (pinfunction "2B_6") (pintype "input"))
    )
    (net (code "112") (name "unconnected-(IC3A-2Y-Pad7)") (class "Default")
      (node (ref "IC3") (pin "7") (pinfunction "2Y_7") (pintype "tri_state"))
    )
    (net (code "113") (name "unconnected-(IC3A-3A-Pad11)") (class "Default")
      (node (ref "IC3") (pin "11") (pinfunction "3A_11") (pintype "input"))
    )
    (net (code "114") (name "unconnected-(IC3A-3B-Pad10)") (class "Default")
      (node (ref "IC3") (pin "10") (pinfunction "3B_10") (pintype "input"))
    )
    (net (code "115") (name "unconnected-(IC3A-3Y-Pad9)") (class "Default")
      (node (ref "IC3") (pin "9") (pinfunction "3Y_9") (pintype "tri_state"))
    )
    (net (code "116") (name "unconnected-(IC3A-4A-Pad14)") (class "Default")
      (node (ref "IC3") (pin "14") (pinfunction "4A_14") (pintype "input"))
    )
    (net (code "117") (name "unconnected-(IC3A-4B-Pad13)") (class "Default")
      (node (ref "IC3") (pin "13") (pinfunction "4B_13") (pintype "input"))
    )
    (net (code "118") (name "unconnected-(IC3A-4Y-Pad12)") (class "Default")
      (node (ref "IC3") (pin "12") (pinfunction "4Y_12") (pintype "tri_state"))
    )
    (net (code "119") (name "unconnected-(IC3A-G-Pad15)") (class "Default")
      (node (ref "IC3") (pin "15") (pinfunction "G_15") (pintype "input"))
    )
    (net (code "120") (name "unconnected-(IC3A-~{A}{slash}B-Pad1)") (class "Default")
      (node (ref "IC3") (pin "1") (pinfunction "~{A}/B_1") (pintype "input"))
    )
    (net (code "121") (name "unconnected-(IC4A-1A-Pad2)") (class "Default")
      (node (ref "IC4") (pin "2") (pinfunction "1A_2") (pintype "input"))
    )
    (net (code "122") (name "unconnected-(IC4A-1B-Pad3)") (class "Default")
      (node (ref "IC4") (pin "3") (pinfunction "1B_3") (pintype "input"))
    )
    (net (code "123") (name "unconnected-(IC4A-1Y-Pad4)") (class "Default")
      (node (ref "IC4") (pin "4") (pinfunction "1Y_4") (pintype "tri_state"))
    )
    (net (code "124") (name "unconnected-(IC4A-2A-Pad5)") (class "Default")
      (node (ref "IC4") (pin "5") (pinfunction "2A_5") (pintype "input"))
    )
    (net (code "125") (name "unconnected-(IC4A-2B-Pad6)") (class "Default")
      (node (ref "IC4") (pin "6") (pinfunction "2B_6") (pintype "input"))
    )
    (net (code "126") (name "unconnected-(IC4A-2Y-Pad7)") (class "Default")
      (node (ref "IC4") (pin "7") (pinfunction "2Y_7") (pintype "tri_state"))
    )
    (net (code "127") (name "unconnected-(IC4A-3A-Pad11)") (class "Default")
      (node (ref "IC4") (pin "11") (pinfunction "3A_11") (pintype "input"))
    )
    (net (code "128") (name "unconnected-(IC4A-3B-Pad10)") (class "Default")
      (node (ref "IC4") (pin "10") (pinfunction "3B_10") (pintype "input"))
    )
    (net (code "129") (name "unconnected-(IC4A-3Y-Pad9)") (class "Default")
      (node (ref "IC4") (pin "9") (pinfunction "3Y_9") (pintype "tri_state"))
    )
    (net (code "130") (name "unconnected-(IC4A-4A-Pad14)") (class "Default")
      (node (ref "IC4") (pin "14") (pinfunction "4A_14") (pintype "input"))
    )
    (net (code "131") (name "unconnected-(IC4A-4B-Pad13)") (class "Default")
      (node (ref "IC4") (pin "13") (pinfunction "4B_13") (pintype "input"))
    )
    (net (code "132") (name "unconnected-(IC4A-4Y-Pad12)") (class "Default")
      (node (ref "IC4") (pin "12") (pinfunction "4Y_12") (pintype "tri_state"))
    )
    (net (code "133") (name "unconnected-(IC4A-G-Pad15)") (class "Default")
      (node (ref "IC4") (pin "15") (pinfunction "G_15") (pintype "input"))
    )
    (net (code "134") (name "unconnected-(IC4A-~{A}{slash}B-Pad1)") (class "Default")
      (node (ref "IC4") (pin "1") (pinfunction "~{A}/B_1") (pintype "input"))
    )
    (net (code "135") (name "unconnected-(IC5A-1A-Pad2)") (class "Default")
      (node (ref "IC5") (pin "2") (pinfunction "1A_2") (pintype "input"))
    )
    (net (code "136") (name "unconnected-(IC5A-1B-Pad3)") (class "Default")
      (node (ref "IC5") (pin "3") (pinfunction "1B_3") (pintype "input"))
    )
    (net (code "137") (name "unconnected-(IC5A-1Y-Pad4)") (class "Default")
      (node (ref "IC5") (pin "4") (pinfunction "1Y_4") (pintype "tri_state"))
    )
    (net (code "138") (name "unconnected-(IC5A-2A-Pad5)") (class "Default")
      (node (ref "IC5") (pin "5") (pinfunction "2A_5") (pintype "input"))
    )
    (net (code "139") (name "unconnected-(IC5A-2B-Pad6)") (class "Default")
      (node (ref "IC5") (pin "6") (pinfunction "2B_6") (pintype "input"))
    )
    (net (code "140") (name "unconnected-(IC5A-2Y-Pad7)") (class "Default")
      (node (ref "IC5") (pin "7") (pinfunction "2Y_7") (pintype "tri_state"))
    )
    (net (code "141") (name "unconnected-(IC5A-3A-Pad11)") (class "Default")
      (node (ref "IC5") (pin "11") (pinfunction "3A_11") (pintype "input"))
    )
    (net (code "142") (name "unconnected-(IC5A-3B-Pad10)") (class "Default")
      (node (ref "IC5") (pin "10") (pinfunction "3B_10") (pintype "input"))
    )
    (net (code "143") (name "unconnected-(IC5A-3Y-Pad9)") (class "Default")
      (node (ref "IC5") (pin "9") (pinfunction "3Y_9") (pintype "tri_state"))
    )
    (net (code "144") (name "unconnected-(IC5A-4A-Pad14)") (class "Default")
      (node (ref "IC5") (pin "14") (pinfunction "4A_14") (pintype "input"))
    )
    (net (code "145") (name "unconnected-(IC5A-4B-Pad13)") (class "Default")
      (node (ref "IC5") (pin "13") (pinfunction "4B_13") (pintype "input"))
    )
    (net (code "146") (name "unconnected-(IC5A-4Y-Pad12)") (class "Default")
      (node (ref "IC5") (pin "12") (pinfunction "4Y_12") (pintype "tri_state"))
    )
    (net (code "147") (name "unconnected-(IC5A-G-Pad15)") (class "Default")
      (node (ref "IC5") (pin "15") (pinfunction "G_15") (pintype "input"))
    )
    (net (code "148") (name "unconnected-(IC5A-~{A}{slash}B-Pad1)") (class "Default")
      (node (ref "IC5") (pin "1") (pinfunction "~{A}/B_1") (pintype "input"))
    )
    (net (code "149") (name "unconnected-(IC6A-1A-Pad2)") (class "Default")
      (node (ref "IC6") (pin "2") (pinfunction "1A_2") (pintype "input"))
    )
    (net (code "150") (name "unconnected-(IC6A-1B-Pad3)") (class "Default")
      (node (ref "IC6") (pin "3") (pinfunction "1B_3") (pintype "input"))
    )
    (net (code "151") (name "unconnected-(IC6A-1Y-Pad4)") (class "Default")
      (node (ref "IC6") (pin "4") (pinfunction "1Y_4") (pintype "tri_state"))
    )
    (net (code "152") (name "unconnected-(IC6A-2A-Pad5)") (class "Default")
      (node (ref "IC6") (pin "5") (pinfunction "2A_5") (pintype "input"))
    )
    (net (code "153") (name "unconnected-(IC6A-2B-Pad6)") (class "Default")
      (node (ref "IC6") (pin "6") (pinfunction "2B_6") (pintype "input"))
    )
    (net (code "154") (name "unconnected-(IC6A-2Y-Pad7)") (class "Default")
      (node (ref "IC6") (pin "7") (pinfunction "2Y_7") (pintype "tri_state"))
    )
    (net (code "155") (name "unconnected-(IC6A-3A-Pad11)") (class "Default")
      (node (ref "IC6") (pin "11") (pinfunction "3A_11") (pintype "input"))
    )
    (net (code "156") (name "unconnected-(IC6A-3B-Pad10)") (class "Default")
      (node (ref "IC6") (pin "10") (pinfunction "3B_10") (pintype "input"))
    )
    (net (code "157") (name "unconnected-(IC6A-3Y-Pad9)") (class "Default")
      (node (ref "IC6") (pin "9") (pinfunction "3Y_9") (pintype "tri_state"))
    )
    (net (code "158") (name "unconnected-(IC6A-4A-Pad14)") (class "Default")
      (node (ref "IC6") (pin "14") (pinfunction "4A_14") (pintype "input"))
    )
    (net (code "159") (name "unconnected-(IC6A-4B-Pad13)") (class "Default")
      (node (ref "IC6") (pin "13") (pinfunction "4B_13") (pintype "input"))
    )
    (net (code "160") (name "unconnected-(IC6A-4Y-Pad12)") (class "Default")
      (node (ref "IC6") (pin "12") (pinfunction "4Y_12") (pintype "tri_state"))
    )
    (net (code "161") (name "unconnected-(IC6A-G-Pad15)") (class "Default")
      (node (ref "IC6") (pin "15") (pinfunction "G_15") (pintype "input"))
    )
    (net (code "162") (name "unconnected-(IC6A-~{A}{slash}B-Pad1)") (class "Default")
      (node (ref "IC6") (pin "1") (pinfunction "~{A}/B_1") (pintype "input"))
    )
    (net (code "163") (name "unconnected-(IC7A-1A-Pad2)") (class "Default")
      (node (ref "IC7") (pin "2") (pinfunction "1A_2") (pintype "input"))
    )
    (net (code "164") (name "unconnected-(IC7A-1B-Pad3)") (class "Default")
      (node (ref "IC7") (pin "3") (pinfunction "1B_3") (pintype "input"))
    )
    (net (code "165") (name "unconnected-(IC7A-1Y-Pad4)") (class "Default")
      (node (ref "IC7") (pin "4") (pinfunction "1Y_4") (pintype "tri_state"))
    )
    (net (code "166") (name "unconnected-(IC7A-2A-Pad5)") (class "Default")
      (node (ref "IC7") (pin "5") (pinfunction "2A_5") (pintype "input"))
    )
    (net (code "167") (name "unconnected-(IC7A-2B-Pad6)") (class "Default")
      (node (ref "IC7") (pin "6") (pinfunction "2B_6") (pintype "input"))
    )
    (net (code "168") (name "unconnected-(IC7A-2Y-Pad7)") (class "Default")
      (node (ref "IC7") (pin "7") (pinfunction "2Y_7") (pintype "tri_state"))
    )
    (net (code "169") (name "unconnected-(IC7A-3A-Pad11)") (class "Default")
      (node (ref "IC7") (pin "11") (pinfunction "3A_11") (pintype "input"))
    )
    (net (code "170") (name "unconnected-(IC7A-3B-Pad10)") (class "Default")
      (node (ref "IC7") (pin "10") (pinfunction "3B_10") (pintype "input"))
    )
    (net (code "171") (name "unconnected-(IC7A-3Y-Pad9)") (class "Default")
      (node (ref "IC7") (pin "9") (pinfunction "3Y_9") (pintype "tri_state"))
    )
    (net (code "172") (name "unconnected-(IC7A-4A-Pad14)") (class "Default")
      (node (ref "IC7") (pin "14") (pinfunction "4A_14") (pintype "input"))
    )
    (net (code "173") (name "unconnected-(IC7A-4B-Pad13)") (class "Default")
      (node (ref "IC7") (pin "13") (pinfunction "4B_13") (pintype "input"))
    )
    (net (code "174") (name "unconnected-(IC7A-4Y-Pad12)") (class "Default")
      (node (ref "IC7") (pin "12") (pinfunction "4Y_12") (pintype "tri_state"))
    )
    (net (code "175") (name "unconnected-(IC7A-G-Pad15)") (class "Default")
      (node (ref "IC7") (pin "15") (pinfunction "G_15") (pintype "input"))
    )
    (net (code "176") (name "unconnected-(IC7A-~{A}{slash}B-Pad1)") (class "Default")
      (node (ref "IC7") (pin "1") (pinfunction "~{A}/B_1") (pintype "input"))
    )
    (net (code "177") (name "unconnected-(IC8A-1A-Pad2)") (class "Default")
      (node (ref "IC8") (pin "2") (pinfunction "1A_2") (pintype "input"))
    )
    (net (code "178") (name "unconnected-(IC8A-1B-Pad3)") (class "Default")
      (node (ref "IC8") (pin "3") (pinfunction "1B_3") (pintype "input"))
    )
    (net (code "179") (name "unconnected-(IC8A-1Y-Pad4)") (class "Default")
      (node (ref "IC8") (pin "4") (pinfunction "1Y_4") (pintype "tri_state"))
    )
    (net (code "180") (name "unconnected-(IC8A-2A-Pad5)") (class "Default")
      (node (ref "IC8") (pin "5") (pinfunction "2A_5") (pintype "input"))
    )
    (net (code "181") (name "unconnected-(IC8A-2B-Pad6)") (class "Default")
      (node (ref "IC8") (pin "6") (pinfunction "2B_6") (pintype "input"))
    )
    (net (code "182") (name "unconnected-(IC8A-2Y-Pad7)") (class "Default")
      (node (ref "IC8") (pin "7") (pinfunction "2Y_7") (pintype "tri_state"))
    )
    (net (code "183") (name "unconnected-(IC8A-3A-Pad11)") (class "Default")
      (node (ref "IC8") (pin "11") (pinfunction "3A_11") (pintype "input"))
    )
    (net (code "184") (name "unconnected-(IC8A-3B-Pad10)") (class "Default")
      (node (ref "IC8") (pin "10") (pinfunction "3B_10") (pintype "input"))
    )
    (net (code "185") (name "unconnected-(IC8A-3Y-Pad9)") (class "Default")
      (node (ref "IC8") (pin "9") (pinfunction "3Y_9") (pintype "tri_state"))
    )
    (net (code "186") (name "unconnected-(IC8A-4A-Pad14)") (class "Default")
      (node (ref "IC8") (pin "14") (pinfunction "4A_14") (pintype "input"))
    )
    (net (code "187") (name "unconnected-(IC8A-4B-Pad13)") (class "Default")
      (node (ref "IC8") (pin "13") (pinfunction "4B_13") (pintype "input"))
    )
    (net (code "188") (name "unconnected-(IC8A-4Y-Pad12)") (class "Default")
      (node (ref "IC8") (pin "12") (pinfunction "4Y_12") (pintype "tri_state"))
    )
    (net (code "189") (name "unconnected-(IC8A-G-Pad15)") (class "Default")
      (node (ref "IC8") (pin "15") (pinfunction "G_15") (pintype "input"))
    )
    (net (code "190") (name "unconnected-(IC8A-~{A}{slash}B-Pad1)") (class "Default")
      (node (ref "IC8") (pin "1") (pinfunction "~{A}/B_1") (pintype "input"))
    )
    (net (code "191") (name "unconnected-(IC9A-1A-Pad2)") (class "Default")
      (node (ref "IC9") (pin "2") (pinfunction "1A_2") (pintype "input"))
    )
    (net (code "192") (name "unconnected-(IC9A-1B-Pad3)") (class "Default")
      (node (ref "IC9") (pin "3") (pinfunction "1B_3") (pintype "input"))
    )
    (net (code "193") (name "unconnected-(IC9A-1Y-Pad4)") (class "Default")
      (node (ref "IC9") (pin "4") (pinfunction "1Y_4") (pintype "tri_state"))
    )
    (net (code "194") (name "unconnected-(IC9A-2A-Pad5)") (class "Default")
      (node (ref "IC9") (pin "5") (pinfunction "2A_5") (pintype "input"))
    )
    (net (code "195") (name "unconnected-(IC9A-2B-Pad6)") (class "Default")
      (node (ref "IC9") (pin "6") (pinfunction "2B_6") (pintype "input"))
    )
    (net (code "196") (name "unconnected-(IC9A-2Y-Pad7)") (class "Default")
      (node (ref "IC9") (pin "7") (pinfunction "2Y_7") (pintype "tri_state"))
    )
    (net (code "197") (name "unconnected-(IC9A-3A-Pad11)") (class "Default")
      (node (ref "IC9") (pin "11") (pinfunction "3A_11") (pintype "input"))
    )
    (net (code "198") (name "unconnected-(IC9A-3B-Pad10)") (class "Default")
      (node (ref "IC9") (pin "10") (pinfunction "3B_10") (pintype "input"))
    )
    (net (code "199") (name "unconnected-(IC9A-3Y-Pad9)") (class "Default")
      (node (ref "IC9") (pin "9") (pinfunction "3Y_9") (pintype "tri_state"))
    )
    (net (code "200") (name "unconnected-(IC9A-4A-Pad14)") (class "Default")
      (node (ref "IC9") (pin "14") (pinfunction "4A_14") (pintype "input"))
    )
    (net (code "201") (name "unconnected-(IC9A-4B-Pad13)") (class "Default")
      (node (ref "IC9") (pin "13") (pinfunction "4B_13") (pintype "input"))
    )
    (net (code "202") (name "unconnected-(IC9A-4Y-Pad12)") (class "Default")
      (node (ref "IC9") (pin "12") (pinfunction "4Y_12") (pintype "tri_state"))
    )
    (net (code "203") (name "unconnected-(IC9A-G-Pad15)") (class "Default")
      (node (ref "IC9") (pin "15") (pinfunction "G_15") (pintype "input"))
    )
    (net (code "204") (name "unconnected-(IC9A-~{A}{slash}B-Pad1)") (class "Default")
      (node (ref "IC9") (pin "1") (pinfunction "~{A}/B_1") (pintype "input"))
    )
    (net (code "205") (name "unconnected-(IC10A-1A-Pad2)") (class "Default")
      (node (ref "IC10") (pin "2") (pinfunction "1A_2") (pintype "input"))
    )
    (net (code "206") (name "unconnected-(IC10A-1B-Pad3)") (class "Default")
      (node (ref "IC10") (pin "3") (pinfunction "1B_3") (pintype "input"))
    )
    (net (code "207") (name "unconnected-(IC10A-1Y-Pad4)") (class "Default")
      (node (ref "IC10") (pin "4") (pinfunction "1Y_4") (pintype "tri_state"))
    )
    (net (code "208") (name "unconnected-(IC10A-2A-Pad5)") (class "Default")
      (node (ref "IC10") (pin "5") (pinfunction "2A_5") (pintype "input"))
    )
    (net (code "209") (name "unconnected-(IC10A-2B-Pad6)") (class "Default")
      (node (ref "IC10") (pin "6") (pinfunction "2B_6") (pintype "input"))
    )
    (net (code "210") (name "unconnected-(IC10A-2Y-Pad7)") (class "Default")
      (node (ref "IC10") (pin "7") (pinfunction "2Y_7") (pintype "tri_state"))
    )
    (net (code "211") (name "unconnected-(IC10A-3A-Pad11)") (class "Default")
      (node (ref "IC10") (pin "11") (pinfunction "3A_11") (pintype "input"))
    )
    (net (code "212") (name "unconnected-(IC10A-3B-Pad10)") (class "Default")
      (node (ref "IC10") (pin "10") (pinfunction "3B_10") (pintype "input"))
    )
    (net (code "213") (name "unconnected-(IC10A-3Y-Pad9)") (class "Default")
      (node (ref "IC10") (pin "9") (pinfunction "3Y_9") (pintype "tri_state"))
    )
    (net (code "214") (name "unconnected-(IC10A-4A-Pad14)") (class "Default")
      (node (ref "IC10") (pin "14") (pinfunction "4A_14") (pintype "input"))
    )
    (net (code "215") (name "unconnected-(IC10A-4B-Pad13)") (class "Default")
      (node (ref "IC10") (pin "13") (pinfunction "4B_13") (pintype "input"))
    )
    (net (code "216") (name "unconnected-(IC10A-4Y-Pad12)") (class "Default")
      (node (ref "IC10") (pin "12") (pinfunction "4Y_12") (pintype "tri_state"))
    )
    (net (code "217") (name "unconnected-(IC10A-G-Pad15)") (class "Default")
      (node (ref "IC10") (pin "15") (pinfunction "G_15") (pintype "input"))
    )
    (net (code "218") (name "unconnected-(IC10A-~{A}{slash}B-Pad1)") (class "Default")
      (node (ref "IC10") (pin "1") (pinfunction "~{A}/B_1") (pintype "input"))
    )
    (net (code "219") (name "unconnected-(IC11A-1A-Pad2)") (class "Default")
      (node (ref "IC11") (pin "2") (pinfunction "1A_2") (pintype "input"))
    )
    (net (code "220") (name "unconnected-(IC11A-1B-Pad3)") (class "Default")
      (node (ref "IC11") (pin "3") (pinfunction "1B_3") (pintype "input"))
    )
    (net (code "221") (name "unconnected-(IC11A-1Y-Pad4)") (class "Default")
      (node (ref "IC11") (pin "4") (pinfunction "1Y_4") (pintype "tri_state"))
    )
    (net (code "222") (name "unconnected-(IC11A-2A-Pad5)") (class "Default")
      (node (ref "IC11") (pin "5") (pinfunction "2A_5") (pintype "input"))
    )
    (net (code "223") (name "unconnected-(IC11A-2B-Pad6)") (class "Default")
      (node (ref "IC11") (pin "6") (pinfunction "2B_6") (pintype "input"))
    )
    (net (code "224") (name "unconnected-(IC11A-2Y-Pad7)") (class "Default")
      (node (ref "IC11") (pin "7") (pinfunction "2Y_7") (pintype "tri_state"))
    )
    (net (code "225") (name "unconnected-(IC11A-3A-Pad11)") (class "Default")
      (node (ref "IC11") (pin "11") (pinfunction "3A_11") (pintype "input"))
    )
    (net (code "226") (name "unconnected-(IC11A-3B-Pad10)") (class "Default")
      (node (ref "IC11") (pin "10") (pinfunction "3B_10") (pintype "input"))
    )
    (net (code "227") (name "unconnected-(IC11A-3Y-Pad9)") (class "Default")
      (node (ref "IC11") (pin "9") (pinfunction "3Y_9") (pintype "tri_state"))
    )
    (net (code "228") (name "unconnected-(IC11A-4A-Pad14)") (class "Default")
      (node (ref "IC11") (pin "14") (pinfunction "4A_14") (pintype "input"))
    )
    (net (code "229") (name "unconnected-(IC11A-4B-Pad13)") (class "Default")
      (node (ref "IC11") (pin "13") (pinfunction "4B_13") (pintype "input"))
    )
    (net (code "230") (name "unconnected-(IC11A-4Y-Pad12)") (class "Default")
      (node (ref "IC11") (pin "12") (pinfunction "4Y_12") (pintype "tri_state"))
    )
    (net (code "231") (name "unconnected-(IC11A-G-Pad15)") (class "Default")
      (node (ref "IC11") (pin "15") (pinfunction "G_15") (pintype "input"))
    )
    (net (code "232") (name "unconnected-(IC11A-~{A}{slash}B-Pad1)") (class "Default")
      (node (ref "IC11") (pin "1") (pinfunction "~{A}/B_1") (pintype "input"))
    )
    (net (code "233") (name "unconnected-(IC12A-1A-Pad2)") (class "Default")
      (node (ref "IC12") (pin "2") (pinfunction "1A_2") (pintype "input"))
    )
    (net (code "234") (name "unconnected-(IC12A-1B-Pad3)") (class "Default")
      (node (ref "IC12") (pin "3") (pinfunction "1B_3") (pintype "input"))
    )
    (net (code "235") (name "unconnected-(IC12A-1Y-Pad4)") (class "Default")
      (node (ref "IC12") (pin "4") (pinfunction "1Y_4") (pintype "tri_state"))
    )
    (net (code "236") (name "unconnected-(IC12A-2A-Pad5)") (class "Default")
      (node (ref "IC12") (pin "5") (pinfunction "2A_5") (pintype "input"))
    )
    (net (code "237") (name "unconnected-(IC12A-2B-Pad6)") (class "Default")
      (node (ref "IC12") (pin "6") (pinfunction "2B_6") (pintype "input"))
    )
    (net (code "238") (name "unconnected-(IC12A-2Y-Pad7)") (class "Default")
      (node (ref "IC12") (pin "7") (pinfunction "2Y_7") (pintype "tri_state"))
    )
    (net (code "239") (name "unconnected-(IC12A-3A-Pad11)") (class "Default")
      (node (ref "IC12") (pin "11") (pinfunction "3A_11") (pintype "input"))
    )
    (net (code "240") (name "unconnected-(IC12A-3B-Pad10)") (class "Default")
      (node (ref "IC12") (pin "10") (pinfunction "3B_10") (pintype "input"))
    )
    (net (code "241") (name "unconnected-(IC12A-3Y-Pad9)") (class "Default")
      (node (ref "IC12") (pin "9") (pinfunction "3Y_9") (pintype "tri_state"))
    )
    (net (code "242") (name "unconnected-(IC12A-4A-Pad14)") (class "Default")
      (node (ref "IC12") (pin "14") (pinfunction "4A_14") (pintype "input"))
    )
    (net (code "243") (name "unconnected-(IC12A-4B-Pad13)") (class "Default")
      (node (ref "IC12") (pin "13") (pinfunction "4B_13") (pintype "input"))
    )
    (net (code "244") (name "unconnected-(IC12A-4Y-Pad12)") (class "Default")
      (node (ref "IC12") (pin "12") (pinfunction "4Y_12") (pintype "tri_state"))
    )
    (net (code "245") (name "unconnected-(IC12A-G-Pad15)") (class "Default")
      (node (ref "IC12") (pin "15") (pinfunction "G_15") (pintype "input"))
    )
    (net (code "246") (name "unconnected-(IC12A-~{A}{slash}B-Pad1)") (class "Default")
      (node (ref "IC12") (pin "1") (pinfunction "~{A}/B_1") (pintype "input"))
    )
    (net (code "247") (name "unconnected-(IC13A-1A-Pad2)") (class "Default")
      (node (ref "IC13") (pin "2") (pinfunction "1A_2") (pintype "input"))
    )
    (net (code "248") (name "unconnected-(IC13A-1B-Pad3)") (class "Default")
      (node (ref "IC13") (pin "3") (pinfunction "1B_3") (pintype "input"))
    )
    (net (code "249") (name "unconnected-(IC13A-1Y-Pad4)") (class "Default")
      (node (ref "IC13") (pin "4") (pinfunction "1Y_4") (pintype "tri_state"))
    )
    (net (code "250") (name "unconnected-(IC13A-2A-Pad5)") (class "Default")
      (node (ref "IC13") (pin "5") (pinfunction "2A_5") (pintype "input"))
    )
    (net (code "251") (name "unconnected-(IC13A-2B-Pad6)") (class "Default")
      (node (ref "IC13") (pin "6") (pinfunction "2B_6") (pintype "input"))
    )
    (net (code "252") (name "unconnected-(IC13A-2Y-Pad7)") (class "Default")
      (node (ref "IC13") (pin "7") (pinfunction "2Y_7") (pintype "tri_state"))
    )
    (net (code "253") (name "unconnected-(IC13A-3A-Pad11)") (class "Default")
      (node (ref "IC13") (pin "11") (pinfunction "3A_11") (pintype "input"))
    )
    (net (code "254") (name "unconnected-(IC13A-3B-Pad10)") (class "Default")
      (node (ref "IC13") (pin "10") (pinfunction "3B_10") (pintype "input"))
    )
    (net (code "255") (name "unconnected-(IC13A-3Y-Pad9)") (class "Default")
      (node (ref "IC13") (pin "9") (pinfunction "3Y_9") (pintype "tri_state"))
    )
    (net (code "256") (name "unconnected-(IC13A-4A-Pad14)") (class "Default")
      (node (ref "IC13") (pin "14") (pinfunction "4A_14") (pintype "input"))
    )
    (net (code "257") (name "unconnected-(IC13A-4B-Pad13)") (class "Default")
      (node (ref "IC13") (pin "13") (pinfunction "4B_13") (pintype "input"))
    )
    (net (code "258") (name "unconnected-(IC13A-4Y-Pad12)") (class "Default")
      (node (ref "IC13") (pin "12") (pinfunction "4Y_12") (pintype "tri_state"))
    )
    (net (code "259") (name "unconnected-(IC13A-G-Pad15)") (class "Default")
      (node (ref "IC13") (pin "15") (pinfunction "G_15") (pintype "input"))
    )
    (net (code "260") (name "unconnected-(IC13A-~{A}{slash}B-Pad1)") (class "Default")
      (node (ref "IC13") (pin "1") (pinfunction "~{A}/B_1") (pintype "input"))
    )
    (net (code "261") (name "unconnected-(IC14A-1A-Pad2)") (class "Default")
      (node (ref "IC14") (pin "2") (pinfunction "1A_2") (pintype "input"))
    )
    (net (code "262") (name "unconnected-(IC14A-1B-Pad3)") (class "Default")
      (node (ref "IC14") (pin "3") (pinfunction "1B_3") (pintype "input"))
    )
    (net (code "263") (name "unconnected-(IC14A-1Y-Pad4)") (class "Default")
      (node (ref "IC14") (pin "4") (pinfunction "1Y_4") (pintype "tri_state"))
    )
    (net (code "264") (name "unconnected-(IC14A-2A-Pad5)") (class "Default")
      (node (ref "IC14") (pin "5") (pinfunction "2A_5") (pintype "input"))
    )
    (net (code "265") (name "unconnected-(IC14A-2B-Pad6)") (class "Default")
      (node (ref "IC14") (pin "6") (pinfunction "2B_6") (pintype "input"))
    )
    (net (code "266") (name "unconnected-(IC14A-2Y-Pad7)") (class "Default")
      (node (ref "IC14") (pin "7") (pinfunction "2Y_7") (pintype "tri_state"))
    )
    (net (code "267") (name "unconnected-(IC14A-3A-Pad11)") (class "Default")
      (node (ref "IC14") (pin "11") (pinfunction "3A_11") (pintype "input"))
    )
    (net (code "268") (name "unconnected-(IC14A-3B-Pad10)") (class "Default")
      (node (ref "IC14") (pin "10") (pinfunction "3B_10") (pintype "input"))
    )
    (net (code "269") (name "unconnected-(IC14A-3Y-Pad9)") (class "Default")
      (node (ref "IC14") (pin "9") (pinfunction "3Y_9") (pintype "tri_state"))
    )
    (net (code "270") (name "unconnected-(IC14A-4A-Pad14)") (class "Default")
      (node (ref "IC14") (pin "14") (pinfunction "4A_14") (pintype "input"))
    )
    (net (code "271") (name "unconnected-(IC14A-4B-Pad13)") (class "Default")
      (node (ref "IC14") (pin "13") (pinfunction "4B_13") (pintype "input"))
    )
    (net (code "272") (name "unconnected-(IC14A-4Y-Pad12)") (class "Default")
      (node (ref "IC14") (pin "12") (pinfunction "4Y_12") (pintype "tri_state"))
    )
    (net (code "273") (name "unconnected-(IC14A-G-Pad15)") (class "Default")
      (node (ref "IC14") (pin "15") (pinfunction "G_15") (pintype "input"))
    )
    (net (code "274") (name "unconnected-(IC14A-~{A}{slash}B-Pad1)") (class "Default")
      (node (ref "IC14") (pin "1") (pinfunction "~{A}/B_1") (pintype "input"))
    )
    (net (code "275") (name "unconnected-(IC15A-1A-Pad2)") (class "Default")
      (node (ref "IC15") (pin "2") (pinfunction "1A_2") (pintype "input"))
    )
    (net (code "276") (name "unconnected-(IC15A-1B-Pad3)") (class "Default")
      (node (ref "IC15") (pin "3") (pinfunction "1B_3") (pintype "input"))
    )
    (net (code "277") (name "unconnected-(IC15A-1Y-Pad4)") (class "Default")
      (node (ref "IC15") (pin "4") (pinfunction "1Y_4") (pintype "tri_state"))
    )
    (net (code "278") (name "unconnected-(IC15A-2A-Pad5)") (class "Default")
      (node (ref "IC15") (pin "5") (pinfunction "2A_5") (pintype "input"))
    )
    (net (code "279") (name "unconnected-(IC15A-2B-Pad6)") (class "Default")
      (node (ref "IC15") (pin "6") (pinfunction "2B_6") (pintype "input"))
    )
    (net (code "280") (name "unconnected-(IC15A-2Y-Pad7)") (class "Default")
      (node (ref "IC15") (pin "7") (pinfunction "2Y_7") (pintype "tri_state"))
    )
    (net (code "281") (name "unconnected-(IC15A-3A-Pad11)") (class "Default")
      (node (ref "IC15") (pin "11") (pinfunction "3A_11") (pintype "input"))
    )
    (net (code "282") (name "unconnected-(IC15A-3B-Pad10)") (class "Default")
      (node (ref "IC15") (pin "10") (pinfunction "3B_10") (pintype "input"))
    )
    (net (code "283") (name "unconnected-(IC15A-3Y-Pad9)") (class "Default")
      (node (ref "IC15") (pin "9") (pinfunction "3Y_9") (pintype "tri_state"))
    )
    (net (code "284") (name "unconnected-(IC15A-4A-Pad14)") (class "Default")
      (node (ref "IC15") (pin "14") (pinfunction "4A_14") (pintype "input"))
    )
    (net (code "285") (name "unconnected-(IC15A-4B-Pad13)") (class "Default")
      (node (ref "IC15") (pin "13") (pinfunction "4B_13") (pintype "input"))
    )
    (net (code "286") (name "unconnected-(IC15A-4Y-Pad12)") (class "Default")
      (node (ref "IC15") (pin "12") (pinfunction "4Y_12") (pintype "tri_state"))
    )
    (net (code "287") (name "unconnected-(IC15A-G-Pad15)") (class "Default")
      (node (ref "IC15") (pin "15") (pinfunction "G_15") (pintype "input"))
    )
    (net (code "288") (name "unconnected-(IC15A-~{A}{slash}B-Pad1)") (class "Default")
      (node (ref "IC15") (pin "1") (pinfunction "~{A}/B_1") (pintype "input"))
    )
    (net (code "289") (name "unconnected-(IC16A-1A-Pad2)") (class "Default")
      (node (ref "IC16") (pin "2") (pinfunction "1A_2") (pintype "input"))
    )
    (net (code "290") (name "unconnected-(IC16A-1B-Pad3)") (class "Default")
      (node (ref "IC16") (pin "3") (pinfunction "1B_3") (pintype "input"))
    )
    (net (code "291") (name "unconnected-(IC16A-1Y-Pad4)") (class "Default")
      (node (ref "IC16") (pin "4") (pinfunction "1Y_4") (pintype "tri_state"))
    )
    (net (code "292") (name "unconnected-(IC16A-2A-Pad5)") (class "Default")
      (node (ref "IC16") (pin "5") (pinfunction "2A_5") (pintype "input"))
    )
    (net (code "293") (name "unconnected-(IC16A-2B-Pad6)") (class "Default")
      (node (ref "IC16") (pin "6") (pinfunction "2B_6") (pintype "input"))
    )
    (net (code "294") (name "unconnected-(IC16A-2Y-Pad7)") (class "Default")
      (node (ref "IC16") (pin "7") (pinfunction "2Y_7") (pintype "tri_state"))
    )
    (net (code "295") (name "unconnected-(IC16A-3A-Pad11)") (class "Default")
      (node (ref "IC16") (pin "11") (pinfunction "3A_11") (pintype "input"))
    )
    (net (code "296") (name "unconnected-(IC16A-3B-Pad10)") (class "Default")
      (node (ref "IC16") (pin "10") (pinfunction "3B_10") (pintype "input"))
    )
    (net (code "297") (name "unconnected-(IC16A-3Y-Pad9)") (class "Default")
      (node (ref "IC16") (pin "9") (pinfunction "3Y_9") (pintype "tri_state"))
    )
    (net (code "298") (name "unconnected-(IC16A-4A-Pad14)") (class "Default")
      (node (ref "IC16") (pin "14") (pinfunction "4A_14") (pintype "input"))
    )
    (net (code "299") (name "unconnected-(IC16A-4B-Pad13)") (class "Default")
      (node (ref "IC16") (pin "13") (pinfunction "4B_13") (pintype "input"))
    )
    (net (code "300") (name "unconnected-(IC16A-4Y-Pad12)") (class "Default")
      (node (ref "IC16") (pin "12") (pinfunction "4Y_12") (pintype "tri_state"))
    )
    (net (code "301") (name "unconnected-(IC16A-G-Pad15)") (class "Default")
      (node (ref "IC16") (pin "15") (pinfunction "G_15") (pintype "input"))
    )
    (net (code "302") (name "unconnected-(IC16A-~{A}{slash}B-Pad1)") (class "Default")
      (node (ref "IC16") (pin "1") (pinfunction "~{A}/B_1") (pintype "input"))
    )
    (net (code "303") (name "unconnected-(IC17A-1A-Pad2)") (class "Default")
      (node (ref "IC17") (pin "2") (pinfunction "1A_2") (pintype "input"))
    )
    (net (code "304") (name "unconnected-(IC17A-1B-Pad3)") (class "Default")
      (node (ref "IC17") (pin "3") (pinfunction "1B_3") (pintype "input"))
    )
    (net (code "305") (name "unconnected-(IC17A-1Y-Pad4)") (class "Default")
      (node (ref "IC17") (pin "4") (pinfunction "1Y_4") (pintype "tri_state"))
    )
    (net (code "306") (name "unconnected-(IC17A-2A-Pad5)") (class "Default")
      (node (ref "IC17") (pin "5") (pinfunction "2A_5") (pintype "input"))
    )
    (net (code "307") (name "unconnected-(IC17A-2B-Pad6)") (class "Default")
      (node (ref "IC17") (pin "6") (pinfunction "2B_6") (pintype "input"))
    )
    (net (code "308") (name "unconnected-(IC17A-2Y-Pad7)") (class "Default")
      (node (ref "IC17") (pin "7") (pinfunction "2Y_7") (pintype "tri_state"))
    )
    (net (code "309") (name "unconnected-(IC17A-3A-Pad11)") (class "Default")
      (node (ref "IC17") (pin "11") (pinfunction "3A_11") (pintype "input"))
    )
    (net (code "310") (name "unconnected-(IC17A-3B-Pad10)") (class "Default")
      (node (ref "IC17") (pin "10") (pinfunction "3B_10") (pintype "input"))
    )
    (net (code "311") (name "unconnected-(IC17A-3Y-Pad9)") (class "Default")
      (node (ref "IC17") (pin "9") (pinfunction "3Y_9") (pintype "tri_state"))
    )
    (net (code "312") (name "unconnected-(IC17A-4A-Pad14)") (class "Default")
      (node (ref "IC17") (pin "14") (pinfunction "4A_14") (pintype "input"))
    )
    (net (code "313") (name "unconnected-(IC17A-4B-Pad13)") (class "Default")
      (node (ref "IC17") (pin "13") (pinfunction "4B_13") (pintype "input"))
    )
    (net (code "314") (name "unconnected-(IC17A-4Y-Pad12)") (class "Default")
      (node (ref "IC17") (pin "12") (pinfunction "4Y_12") (pintype "tri_state"))
    )
    (net (code "315") (name "unconnected-(IC17A-G-Pad15)") (class "Default")
      (node (ref "IC17") (pin "15") (pinfunction "G_15") (pintype "input"))
    )
    (net (code "316") (name "unconnected-(IC17A-~{A}{slash}B-Pad1)") (class "Default")
      (node (ref "IC17") (pin "1") (pinfunction "~{A}/B_1") (pintype "input"))
    )
    (net (code "317") (name "unconnected-(IC18A-1A-Pad2)") (class "Default")
      (node (ref "IC18") (pin "2") (pinfunction "1A_2") (pintype "input"))
    )
    (net (code "318") (name "unconnected-(IC18A-1B-Pad3)") (class "Default")
      (node (ref "IC18") (pin "3") (pinfunction "1B_3") (pintype "input"))
    )
    (net (code "319") (name "unconnected-(IC18A-1Y-Pad4)") (class "Default")
      (node (ref "IC18") (pin "4") (pinfunction "1Y_4") (pintype "tri_state"))
    )
    (net (code "320") (name "unconnected-(IC18A-2A-Pad5)") (class "Default")
      (node (ref "IC18") (pin "5") (pinfunction "2A_5") (pintype "input"))
    )
    (net (code "321") (name "unconnected-(IC18A-2B-Pad6)") (class "Default")
      (node (ref "IC18") (pin "6") (pinfunction "2B_6") (pintype "input"))
    )
    (net (code "322") (name "unconnected-(IC18A-2Y-Pad7)") (class "Default")
      (node (ref "IC18") (pin "7") (pinfunction "2Y_7") (pintype "tri_state"))
    )
    (net (code "323") (name "unconnected-(IC18A-3A-Pad11)") (class "Default")
      (node (ref "IC18") (pin "11") (pinfunction "3A_11") (pintype "input"))
    )
    (net (code "324") (name "unconnected-(IC18A-3B-Pad10)") (class "Default")
      (node (ref "IC18") (pin "10") (pinfunction "3B_10") (pintype "input"))
    )
    (net (code "325") (name "unconnected-(IC18A-3Y-Pad9)") (class "Default")
      (node (ref "IC18") (pin "9") (pinfunction "3Y_9") (pintype "tri_state"))
    )
    (net (code "326") (name "unconnected-(IC18A-4A-Pad14)") (class "Default")
      (node (ref "IC18") (pin "14") (pinfunction "4A_14") (pintype "input"))
    )
    (net (code "327") (name "unconnected-(IC18A-4B-Pad13)") (class "Default")
      (node (ref "IC18") (pin "13") (pinfunction "4B_13") (pintype "input"))
    )
    (net (code "328") (name "unconnected-(IC18A-4Y-Pad12)") (class "Default")
      (node (ref "IC18") (pin "12") (pinfunction "4Y_12") (pintype "tri_state"))
    )
    (net (code "329") (name "unconnected-(IC18A-G-Pad15)") (class "Default")
      (node (ref "IC18") (pin "15") (pinfunction "G_15") (pintype "input"))
    )
    (net (code "330") (name "unconnected-(IC18A-~{A}{slash}B-Pad1)") (class "Default")
      (node (ref "IC18") (pin "1") (pinfunction "~{A}/B_1") (pintype "input"))
    )
    (net (code "331") (name "unconnected-(IC19A-1A-Pad2)") (class "Default")
      (node (ref "IC19") (pin "2") (pinfunction "1A_2") (pintype "input"))
    )
    (net (code "332") (name "unconnected-(IC19A-1B-Pad3)") (class "Default")
      (node (ref "IC19") (pin "3") (pinfunction "1B_3") (pintype "input"))
    )
    (net (code "333") (name "unconnected-(IC19A-1Y-Pad4)") (class "Default")
      (node (ref "IC19") (pin "4") (pinfunction "1Y_4") (pintype "tri_state"))
    )
    (net (code "334") (name "unconnected-(IC19A-2A-Pad5)") (class "Default")
      (node (ref "IC19") (pin "5") (pinfunction "2A_5") (pintype "input"))
    )
    (net (code "335") (name "unconnected-(IC19A-2B-Pad6)") (class "Default")
      (node (ref "IC19") (pin "6") (pinfunction "2B_6") (pintype "input"))
    )
    (net (code "336") (name "unconnected-(IC19A-2Y-Pad7)") (class "Default")
      (node (ref "IC19") (pin "7") (pinfunction "2Y_7") (pintype "tri_state"))
    )
    (net (code "337") (name "unconnected-(IC19A-3A-Pad11)") (class "Default")
      (node (ref "IC19") (pin "11") (pinfunction "3A_11") (pintype "input"))
    )
    (net (code "338") (name "unconnected-(IC19A-3B-Pad10)") (class "Default")
      (node (ref "IC19") (pin "10") (pinfunction "3B_10") (pintype "input"))
    )
    (net (code "339") (name "unconnected-(IC19A-3Y-Pad9)") (class "Default")
      (node (ref "IC19") (pin "9") (pinfunction "3Y_9") (pintype "tri_state"))
    )
    (net (code "340") (name "unconnected-(IC19A-4A-Pad14)") (class "Default")
      (node (ref "IC19") (pin "14") (pinfunction "4A_14") (pintype "input"))
    )
    (net (code "341") (name "unconnected-(IC19A-4B-Pad13)") (class "Default")
      (node (ref "IC19") (pin "13") (pinfunction "4B_13") (pintype "input"))
    )
    (net (code "342") (name "unconnected-(IC19A-4Y-Pad12)") (class "Default")
      (node (ref "IC19") (pin "12") (pinfunction "4Y_12") (pintype "tri_state"))
    )
    (net (code "343") (name "unconnected-(IC19A-G-Pad15)") (class "Default")
      (node (ref "IC19") (pin "15") (pinfunction "G_15") (pintype "input"))
    )
    (net (code "344") (name "unconnected-(IC19A-~{A}{slash}B-Pad1)") (class "Default")
      (node (ref "IC19") (pin "1") (pinfunction "~{A}/B_1") (pintype "input"))
    )
    (net (code "345") (name "unconnected-(IC20A-1A-Pad2)") (class "Default")
      (node (ref "IC20") (pin "2") (pinfunction "1A_2") (pintype "input"))
    )
    (net (code "346") (name "unconnected-(IC20A-1B-Pad3)") (class "Default")
      (node (ref "IC20") (pin "3") (pinfunction "1B_3") (pintype "input"))
    )
    (net (code "347") (name "unconnected-(IC20A-1Y-Pad4)") (class "Default")
      (node (ref "IC20") (pin "4") (pinfunction "1Y_4") (pintype "tri_state"))
    )
    (net (code "348") (name "unconnected-(IC20A-2A-Pad5)") (class "Default")
      (node (ref "IC20") (pin "5") (pinfunction "2A_5") (pintype "input"))
    )
    (net (code "349") (name "unconnected-(IC20A-2B-Pad6)") (class "Default")
      (node (ref "IC20") (pin "6") (pinfunction "2B_6") (pintype "input"))
    )
    (net (code "350") (name "unconnected-(IC20A-2Y-Pad7)") (class "Default")
      (node (ref "IC20") (pin "7") (pinfunction "2Y_7") (pintype "tri_state"))
    )
    (net (code "351") (name "unconnected-(IC20A-3A-Pad11)") (class "Default")
      (node (ref "IC20") (pin "11") (pinfunction "3A_11") (pintype "input"))
    )
    (net (code "352") (name "unconnected-(IC20A-3B-Pad10)") (class "Default")
      (node (ref "IC20") (pin "10") (pinfunction "3B_10") (pintype "input"))
    )
    (net (code "353") (name "unconnected-(IC20A-3Y-Pad9)") (class "Default")
      (node (ref "IC20") (pin "9") (pinfunction "3Y_9") (pintype "tri_state"))
    )
    (net (code "354") (name "unconnected-(IC20A-4A-Pad14)") (class "Default")
      (node (ref "IC20") (pin "14") (pinfunction "4A_14") (pintype "input"))
    )
    (net (code "355") (name "unconnected-(IC20A-4B-Pad13)") (class "Default")
      (node (ref "IC20") (pin "13") (pinfunction "4B_13") (pintype "input"))
    )
    (net (code "356") (name "unconnected-(IC20A-4Y-Pad12)") (class "Default")
      (node (ref "IC20") (pin "12") (pinfunction "4Y_12") (pintype "tri_state"))
    )
    (net (code "357") (name "unconnected-(IC20A-G-Pad15)") (class "Default")
      (node (ref "IC20") (pin "15") (pinfunction "G_15") (pintype "input"))
    )
    (net (code "358") (name "unconnected-(IC20A-~{A}{slash}B-Pad1)") (class "Default")
      (node (ref "IC20") (pin "1") (pinfunction "~{A}/B_1") (pintype "input"))
    )
    (net (code "359") (name "unconnected-(R1-Pad1)") (class "Default")
      (node (ref "R1") (pin "1") (pinfunction "1_1") (pintype "passive"))
    )
    (net (code "360") (name "unconnected-(R57-Pad1)") (class "Default")
      (node (ref "R57") (pin "1") (pinfunction "1_1") (pintype "passive"))
    )
    (net (code "361") (name "unconnected-(R65-Pad1)") (class "Default")
      (node (ref "R65") (pin "1") (pinfunction "1_1") (pintype "passive"))
    )
    (net (code "362") (name "unconnected-(R73-Pad1)") (class "Default")
      (node (ref "R73") (pin "1") (pinfunction "1_1") (pintype "passive"))
    )
    (net (code "363") (name "unconnected-(U$1-Pad1)") (class "Default")
      (node (ref "U$1") (pin "1") (pinfunction "1_1") (pintype "passive"))
    )
    (net (code "364") (name "unconnected-(U$1-Pad2)") (class "Default")
      (node (ref "U$1") (pin "2") (pinfunction "2_2") (pintype "passive"))
    )
    (net (code "365") (name "unconnected-(U$1-Pad3)") (class "Default")
      (node (ref "U$1") (pin "3") (pinfunction "3_3") (pintype "passive"))
    )
    (net (code "366") (name "unconnected-(U$1-Pad4)") (class "Default")
      (node (ref "U$1") (pin "4") (pinfunction "4_4") (pintype "passive"))
    )
    (net (code "367") (name "unconnected-(U$1-Pad5)") (class "Default")
      (node (ref "U$1") (pin "5") (pinfunction "5_5") (pintype "passive"))
    )
    (net (code "368") (name "unconnected-(U$1-Pad6)") (class "Default")
      (node (ref "U$1") (pin "6") (pinfunction "6_6") (pintype "passive"))
    )
    (net (code "369") (name "unconnected-(U$1-Pad7)") (class "Default")
      (node (ref "U$1") (pin "7") (pinfunction "7_7") (pintype "passive"))
    )
    (net (code "370") (name "unconnected-(U$1-Pad8)") (class "Default")
      (node (ref "U$1") (pin "8") (pinfunction "8_8") (pintype "passive"))
    )
    (net (code "371") (name "unconnected-(U$2-Pad1)") (class "Default")
      (node (ref "U$2") (pin "1") (pinfunction "1_1") (pintype "passive"))
    )
    (net (code "372") (name "unconnected-(U$2-Pad2)") (class "Default")
      (node (ref "U$2") (pin "2") (pinfunction "2_2") (pintype "passive"))
    )
    (net (code "373") (name "unconnected-(U$2-Pad3)") (class "Default")
      (node (ref "U$2") (pin "3") (pinfunction "3_3") (pintype "passive"))
    )
    (net (code "374") (name "unconnected-(U$2-Pad4)") (class "Default")
      (node (ref "U$2") (pin "4") (pinfunction "4_4") (pintype "passive"))
    )
    (net (code "375") (name "unconnected-(U$2-Pad5)") (class "Default")
      (node (ref "U$2") (pin "5") (pinfunction "5_5") (pintype "passive"))
    )
    (net (code "376") (name "unconnected-(U$2-Pad6)") (class "Default")
      (node (ref "U$2") (pin "6") (pinfunction "6_6") (pintype "passive"))
    )
    (net (code "377") (name "unconnected-(U$2-Pad7)") (class "Default")
      (node (ref "U$2") (pin "7") (pinfunction "7_7") (pintype "passive"))
    )
    (net (code "378") (name "unconnected-(U$2-Pad8)") (class "Default")
      (node (ref "U$2") (pin "8") (pinfunction "8_8") (pintype "passive"))
    )
    (net (code "379") (name "unconnected-(U$3-Pad1)") (class "Default")
      (node (ref "U$3") (pin "1") (pinfunction "1_1") (pintype "passive"))
    )
    (net (code "380") (name "unconnected-(U$3-Pad2)") (class "Default")
      (node (ref "U$3") (pin "2") (pinfunction "2_2") (pintype "passive"))
    )
    (net (code "381") (name "unconnected-(U$3-Pad3)") (class "Default")
      (node (ref "U$3") (pin "3") (pinfunction "3_3") (pintype "passive"))
    )
    (net (code "382") (name "unconnected-(U$3-Pad4)") (class "Default")
      (node (ref "U$3") (pin "4") (pinfunction "4_4") (pintype "passive"))
    )
    (net (code "383") (name "unconnected-(U$3-Pad5)") (class "Default")
      (node (ref "U$3") (pin "5") (pinfunction "5_5") (pintype "passive"))
    )
    (net (code "384") (name "unconnected-(U$3-Pad6)") (class "Default")
      (node (ref "U$3") (pin "6") (pinfunction "6_6") (pintype "passive"))
    )
    (net (code "385") (name "unconnected-(U$3-Pad7)") (class "Default")
      (node (ref "U$3") (pin "7") (pinfunction "7_7") (pintype "passive"))
    )
    (net (code "386") (name "unconnected-(U$3-Pad8)") (class "Default")
      (node (ref "U$3") (pin "8") (pinfunction "8_8") (pintype "passive"))
    )
    (net (code "387") (name "unconnected-(U$4-Pad1)") (class "Default")
      (node (ref "U$4") (pin "1") (pinfunction "1_1") (pintype "passive"))
    )
    (net (code "388") (name "unconnected-(U$4-Pad2)") (class "Default")
      (node (ref "U$4") (pin "2") (pinfunction "2_2") (pintype "passive"))
    )
    (net (code "389") (name "unconnected-(U$4-Pad3)") (class "Default")
      (node (ref "U$4") (pin "3") (pinfunction "3_3") (pintype "passive"))
    )
    (net (code "390") (name "unconnected-(U$4-Pad4)") (class "Default")
      (node (ref "U$4") (pin "4") (pinfunction "4_4") (pintype "passive"))
    )
    (net (code "391") (name "unconnected-(U$4-Pad5)") (class "Default")
      (node (ref "U$4") (pin "5") (pinfunction "5_5") (pintype "passive"))
    )
    (net (code "392") (name "unconnected-(U$4-Pad6)") (class "Default")
      (node (ref "U$4") (pin "6") (pinfunction "6_6") (pintype "passive"))
    )
    (net (code "393") (name "unconnected-(U$4-Pad7)") (class "Default")
      (node (ref "U$4") (pin "7") (pinfunction "7_7") (pintype "passive"))
    )
    (net (code "394") (name "unconnected-(U$4-Pad8)") (class "Default")
      (node (ref "U$4") (pin "8") (pinfunction "8_8") (pintype "passive"))
    )
    (net (code "395") (name "unconnected-(U$5-Pad1)") (class "Default")
      (node (ref "U$5") (pin "1") (pinfunction "1_1") (pintype "passive"))
    )
    (net (code "396") (name "unconnected-(U$5-Pad2)") (class "Default")
      (node (ref "U$5") (pin "2") (pinfunction "2_2") (pintype "passive"))
    )
    (net (code "397") (name "unconnected-(U$5-Pad3)") (class "Default")
      (node (ref "U$5") (pin "3") (pinfunction "3_3") (pintype "passive"))
    )
    (net (code "398") (name "unconnected-(U$5-Pad4)") (class "Default")
      (node (ref "U$5") (pin "4") (pinfunction "4_4") (pintype "passive"))
    )
    (net (code "399") (name "unconnected-(U$5-Pad5)") (class "Default")
      (node (ref "U$5") (pin "5") (pinfunction "5_5") (pintype "passive"))
    )
    (net (code "400") (name "unconnected-(U$5-Pad6)") (class "Default")
      (node (ref "U$5") (pin "6") (pinfunction "6_6") (pintype "passive"))
    )
    (net (code "401") (name "unconnected-(U$5-Pad7)") (class "Default")
      (node (ref "U$5") (pin "7") (pinfunction "7_7") (pintype "passive"))
    )
    (net (code "402") (name "unconnected-(U$5-Pad8)") (class "Default")
      (node (ref "U$5") (pin "8") (pinfunction "8_8") (pintype "passive"))
    )
    (net (code "403") (name "unconnected-(U$6-Pad1)") (class "Default")
      (node (ref "U$6") (pin "1") (pinfunction "1_1") (pintype "passive"))
    )
    (net (code "404") (name "unconnected-(U$6-Pad2)") (class "Default")
      (node (ref "U$6") (pin "2") (pinfunction "2_2") (pintype "passive"))
    )
    (net (code "405") (name "unconnected-(U$6-Pad3)") (class "Default")
      (node (ref "U$6") (pin "3") (pinfunction "3_3") (pintype "passive"))
    )
    (net (code "406") (name "unconnected-(U$6-Pad4)") (class "Default")
      (node (ref "U$6") (pin "4") (pinfunction "4_4") (pintype "passive"))
    )
    (net (code "407") (name "unconnected-(U$6-Pad5)") (class "Default")
      (node (ref "U$6") (pin "5") (pinfunction "5_5") (pintype "passive"))
    )
    (net (code "408") (name "unconnected-(U$6-Pad6)") (class "Default")
      (node (ref "U$6") (pin "6") (pinfunction "6_6") (pintype "passive"))
    )
    (net (code "409") (name "unconnected-(U$6-Pad7)") (class "Default")
      (node (ref "U$6") (pin "7") (pinfunction "7_7") (pintype "passive"))
    )
    (net (code "410") (name "unconnected-(U$6-Pad8)") (class "Default")
      (node (ref "U$6") (pin "8") (pinfunction "8_8") (pintype "passive"))
    )
  )
)
